# AD9910_Finished_3rd.net
KiCad netlist of a schematic drawn in EAGLE
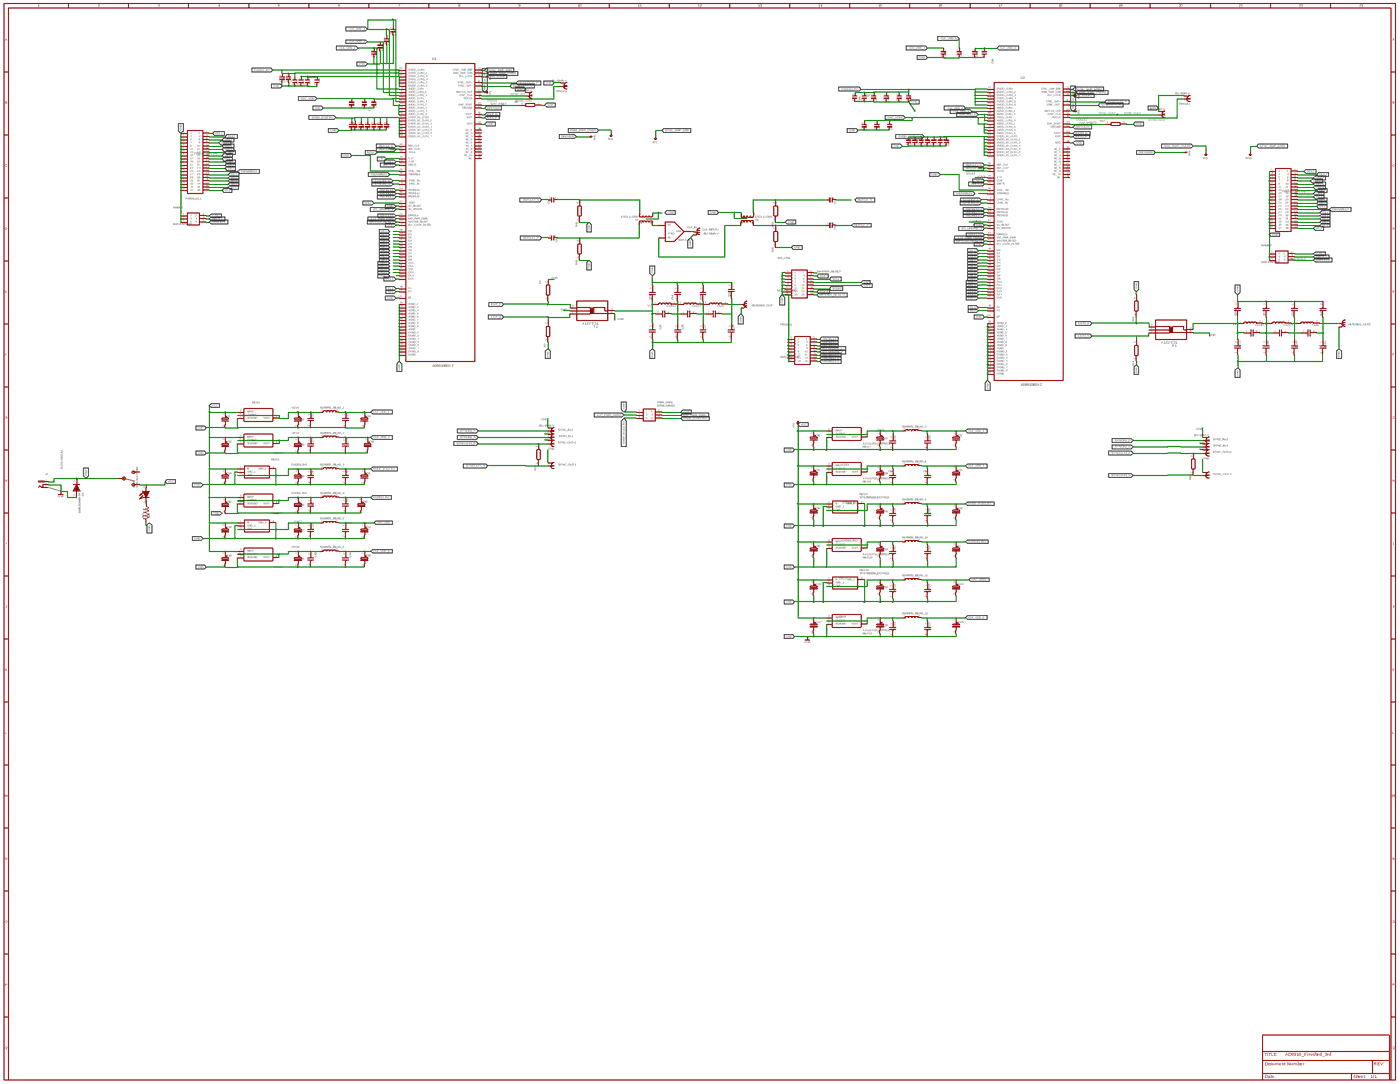
[diagram p0: schematic, sheet 1, overview]
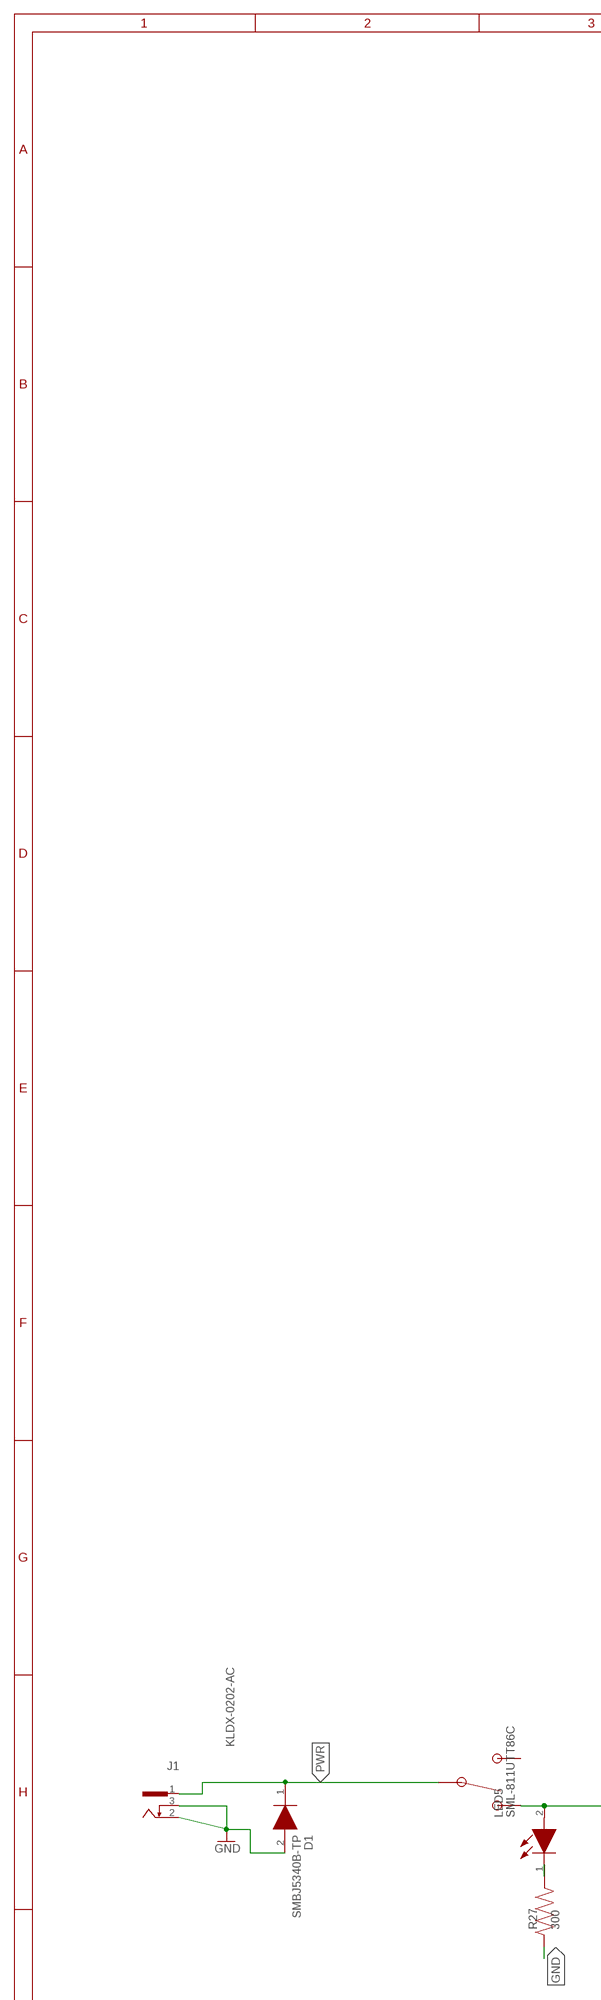
[diagram p1: schematic, sheet 1, part 1 of 7]
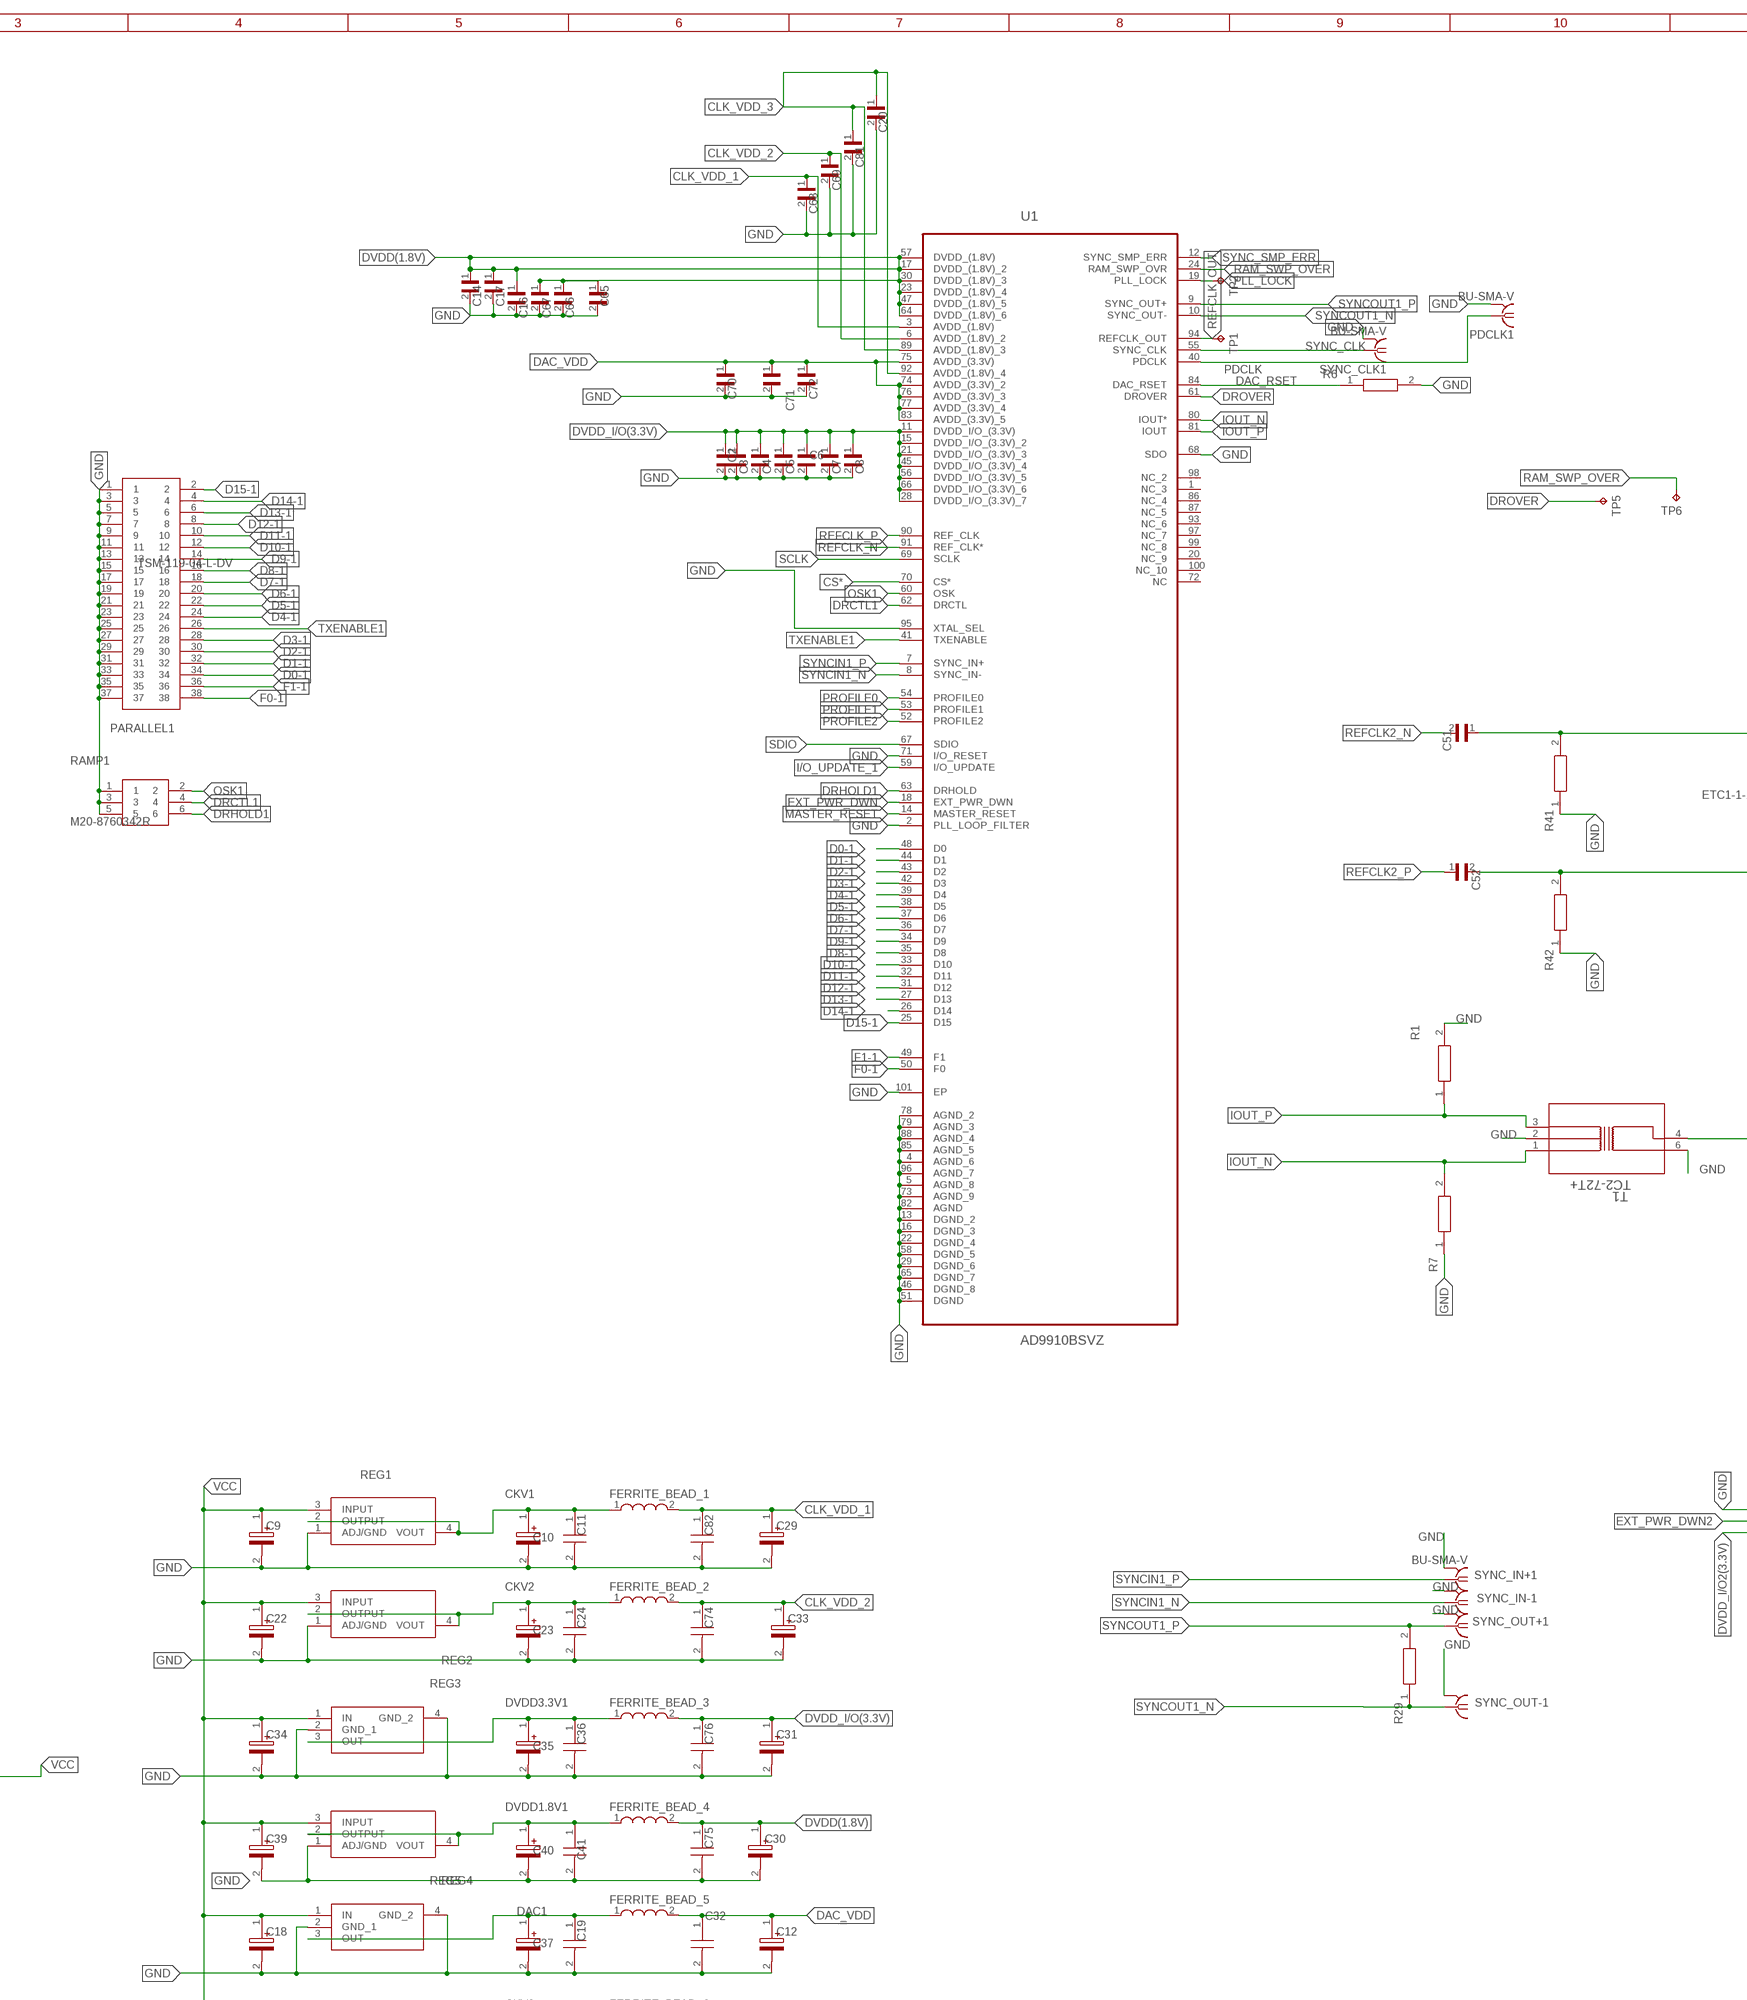
[diagram p2: schematic, sheet 1, part 2 of 7]
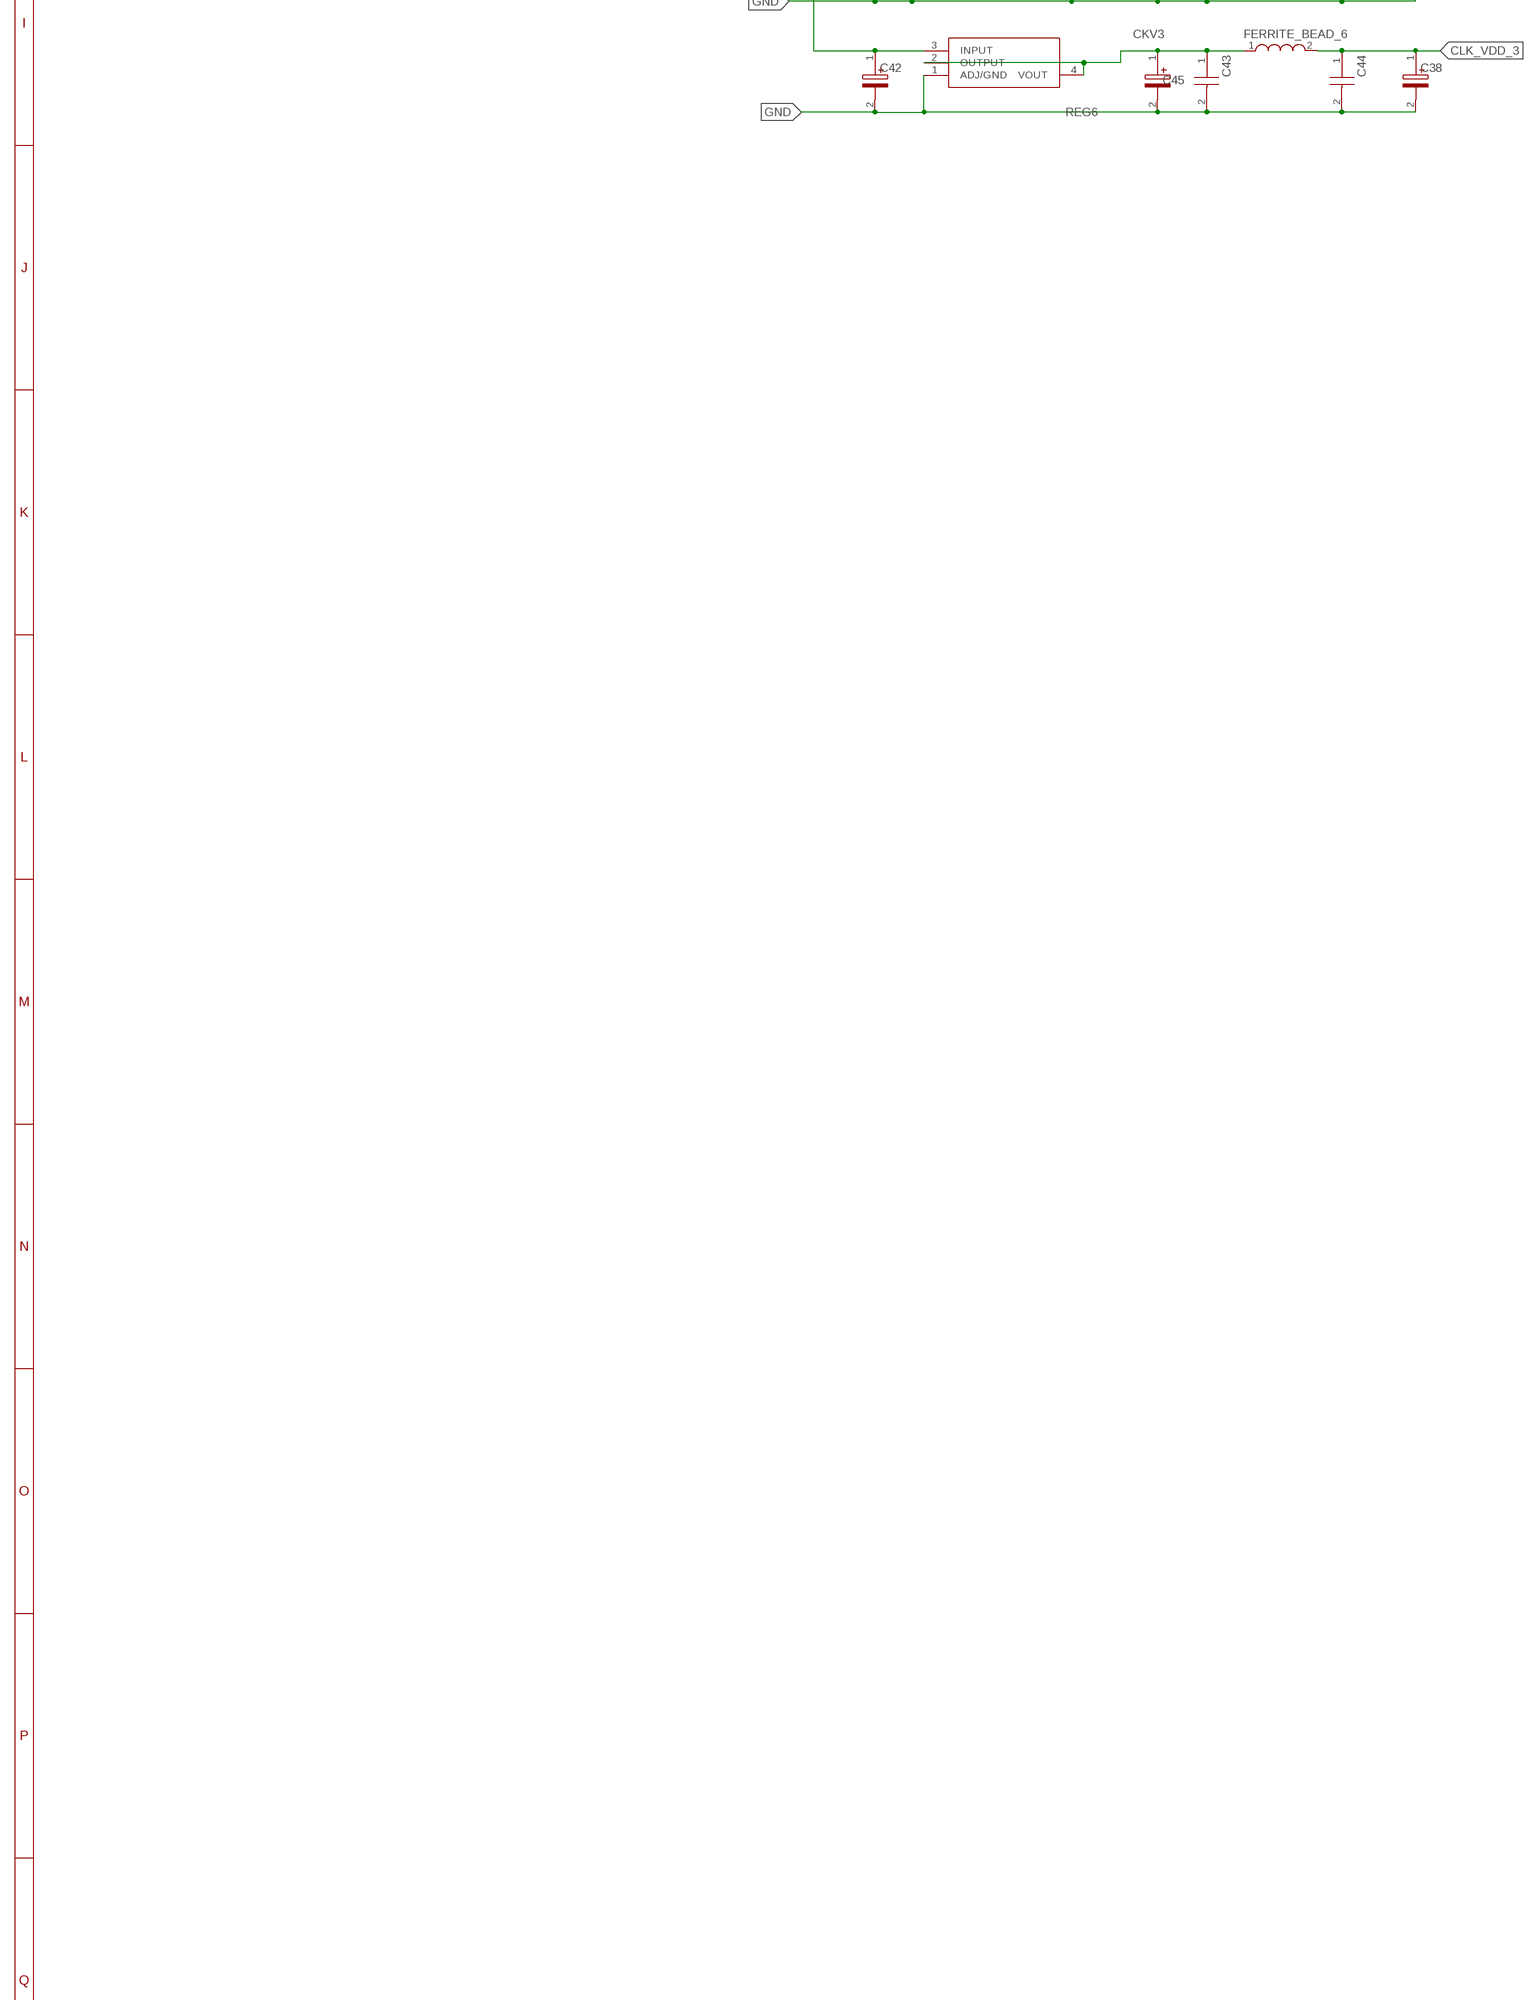
[diagram p3: schematic, sheet 1, part 3 of 7]
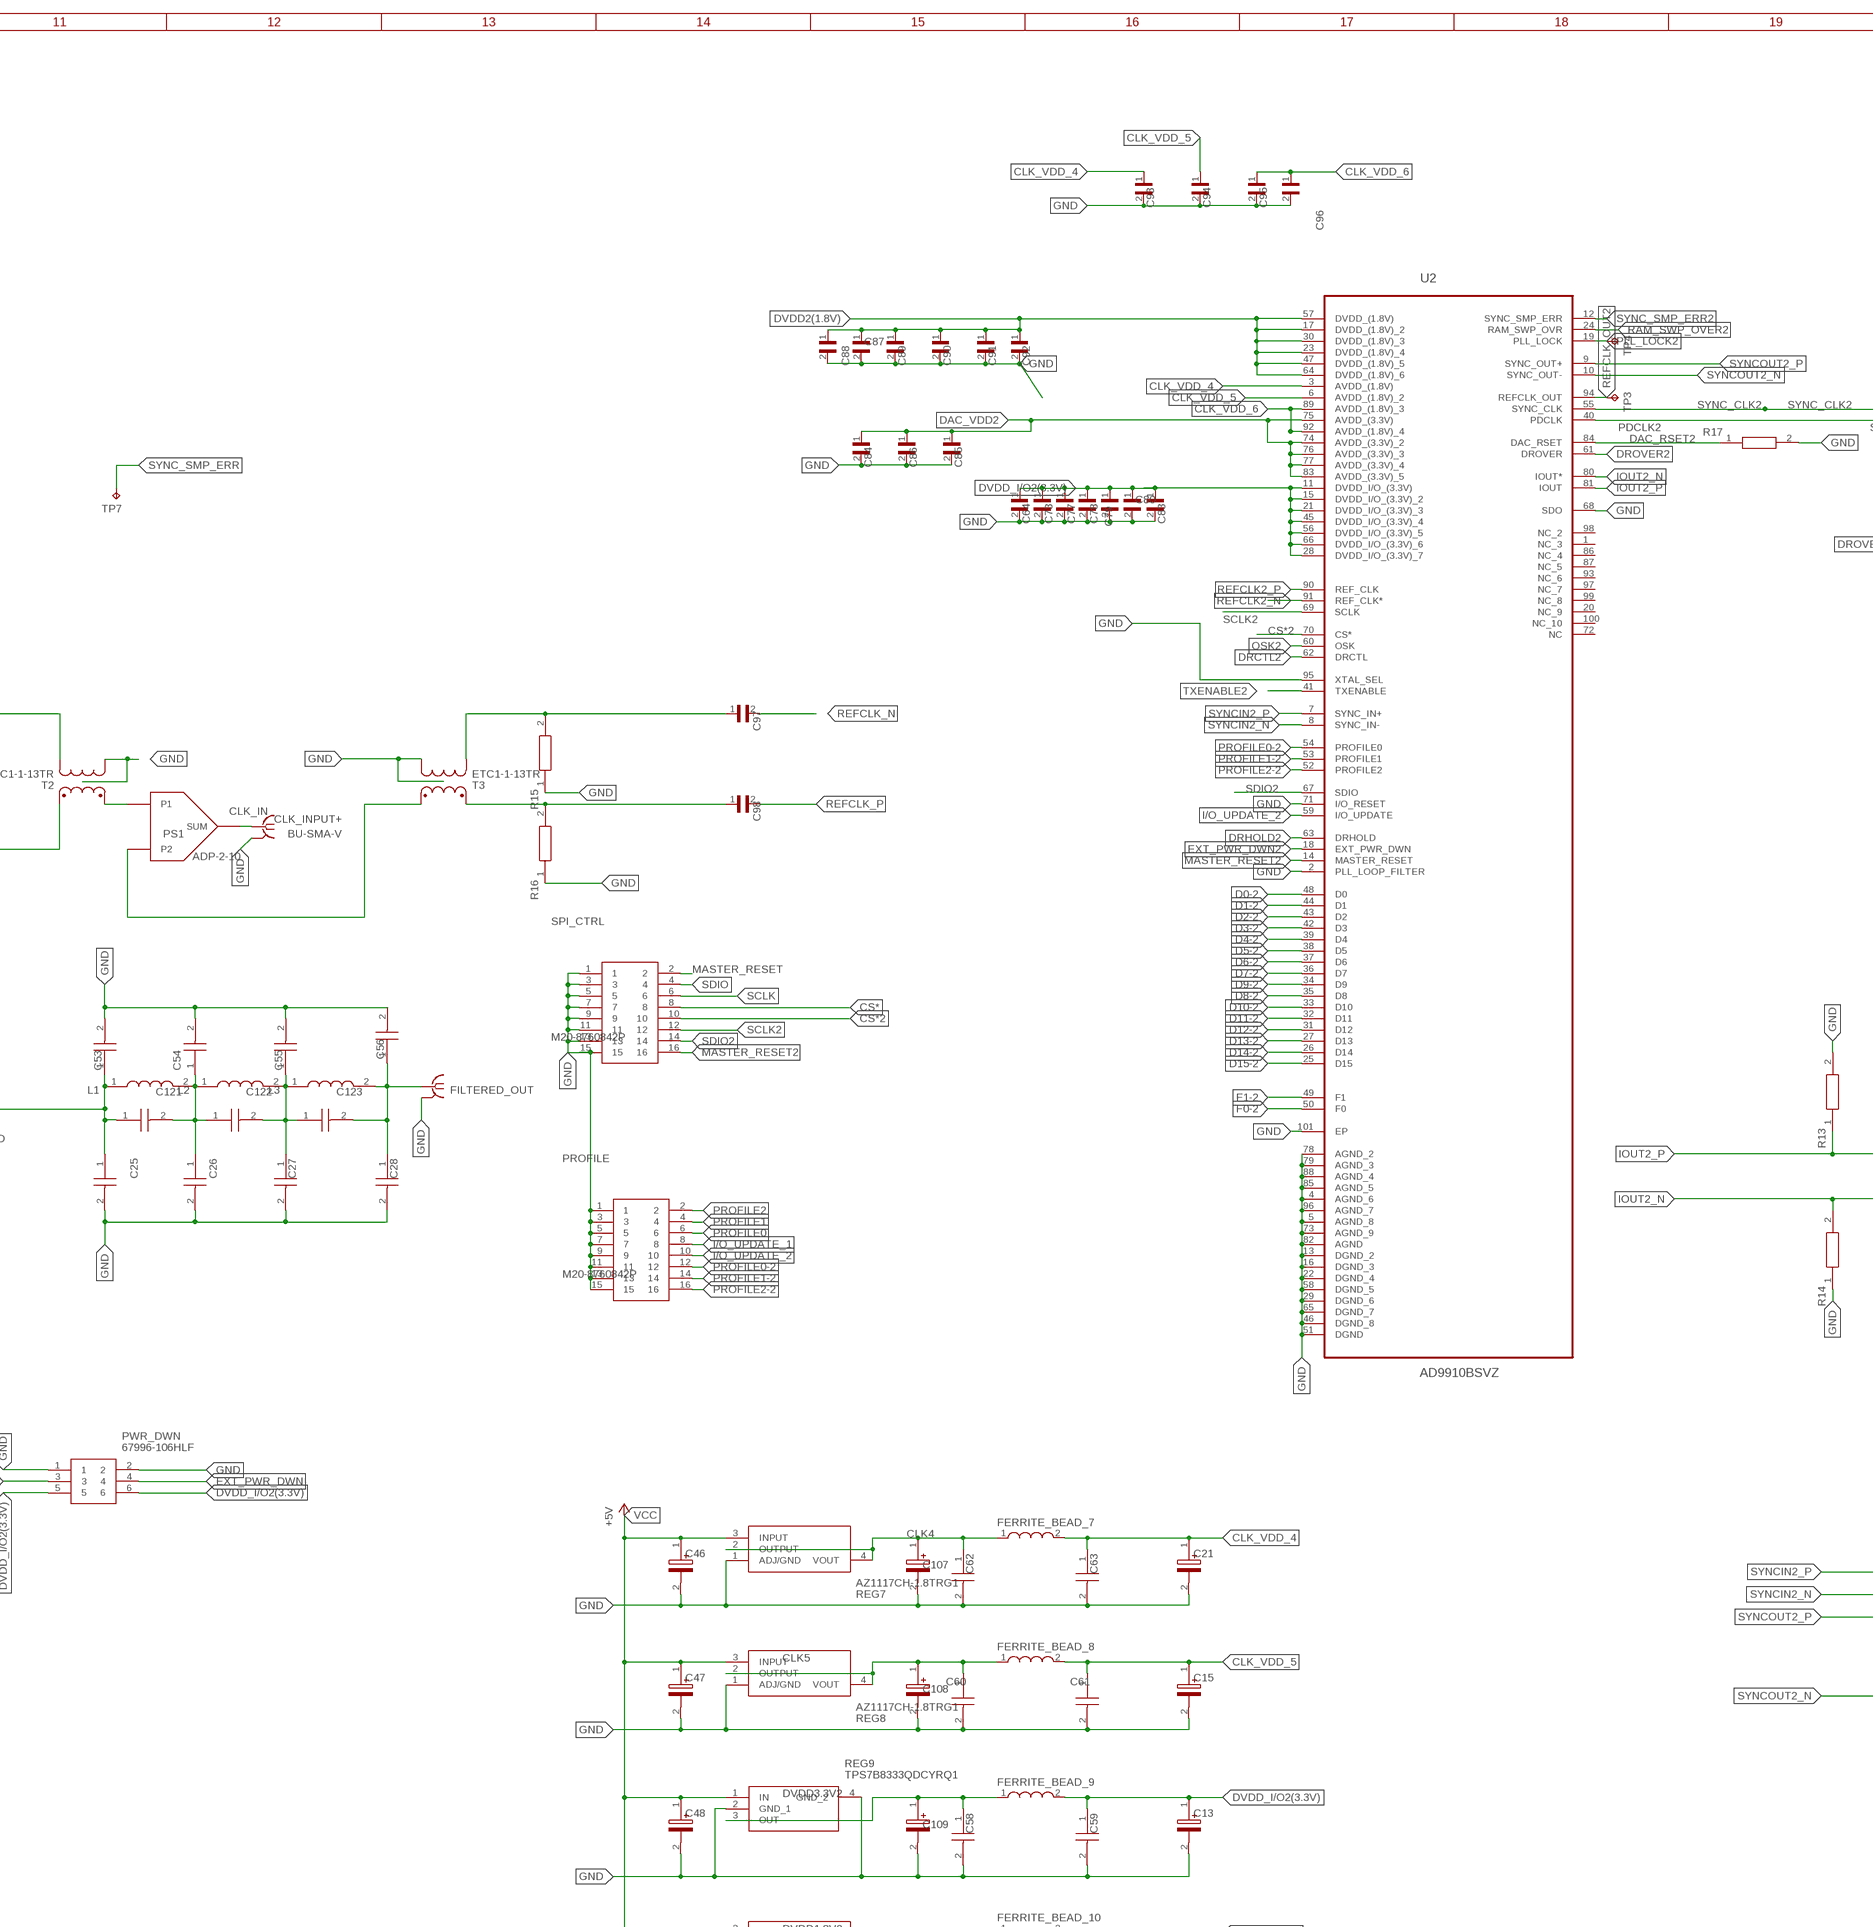
[diagram p4: schematic, sheet 1, part 4 of 7]
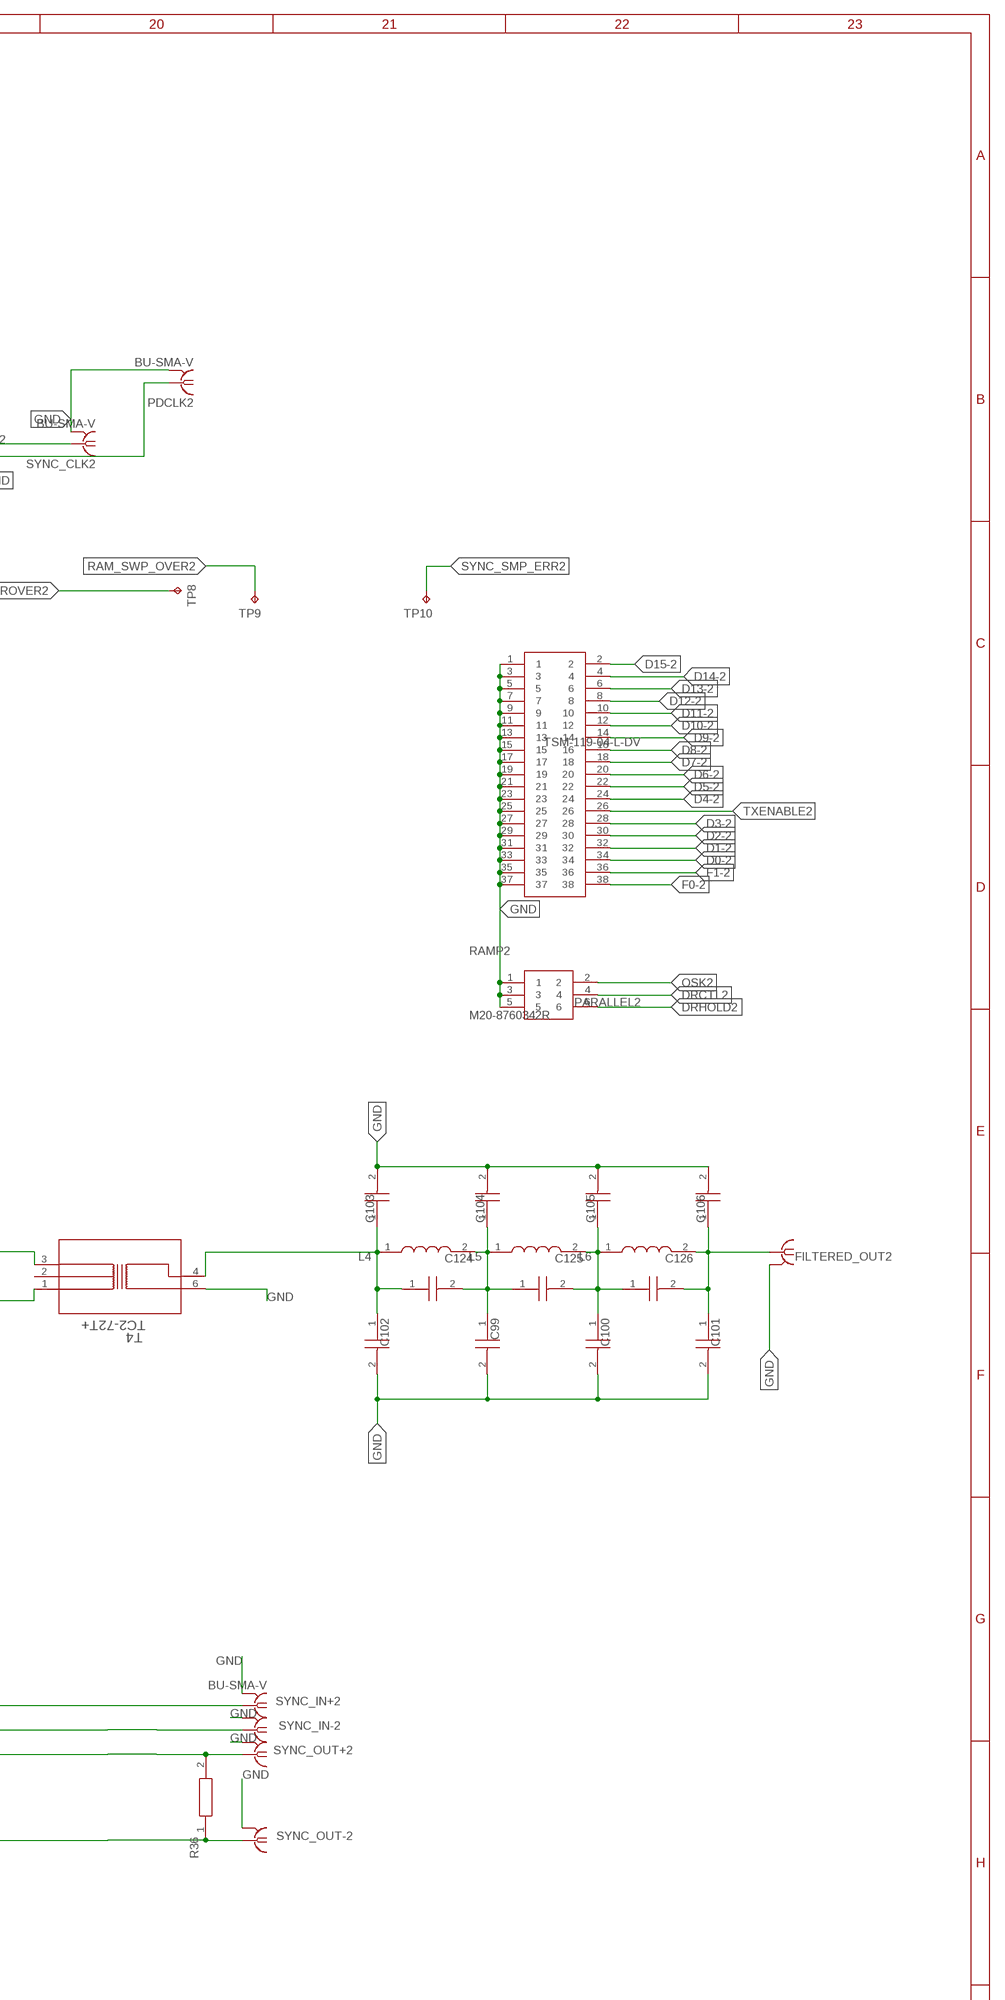
[diagram p5: schematic, sheet 1, part 5 of 7]
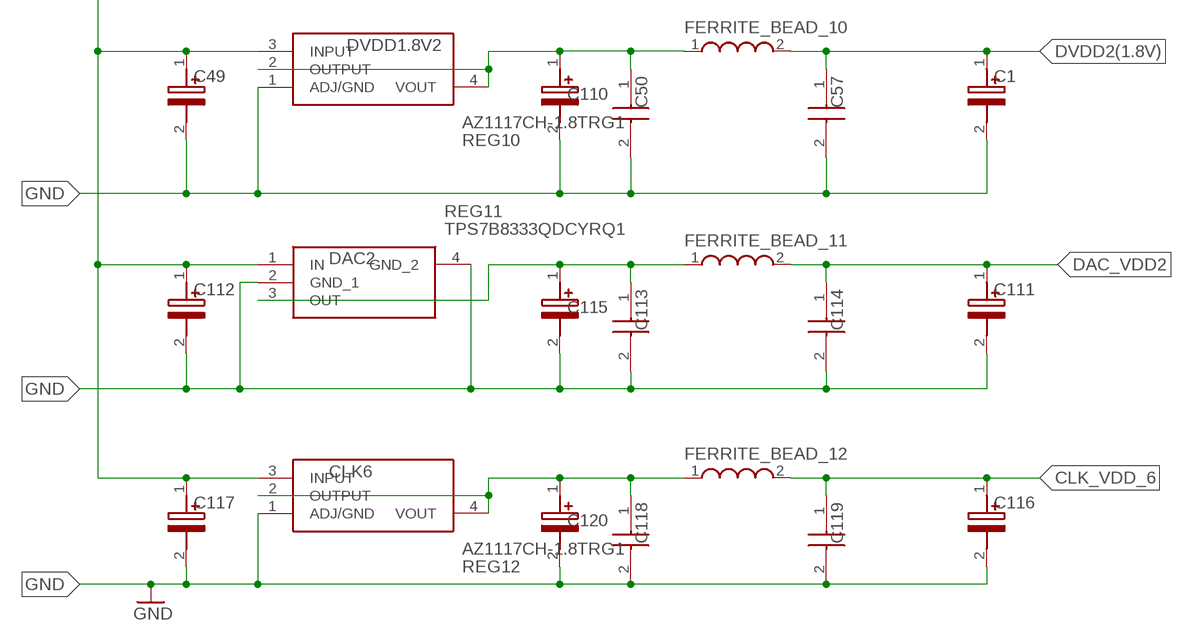
[diagram p6: schematic, sheet 1, part 6 of 7]
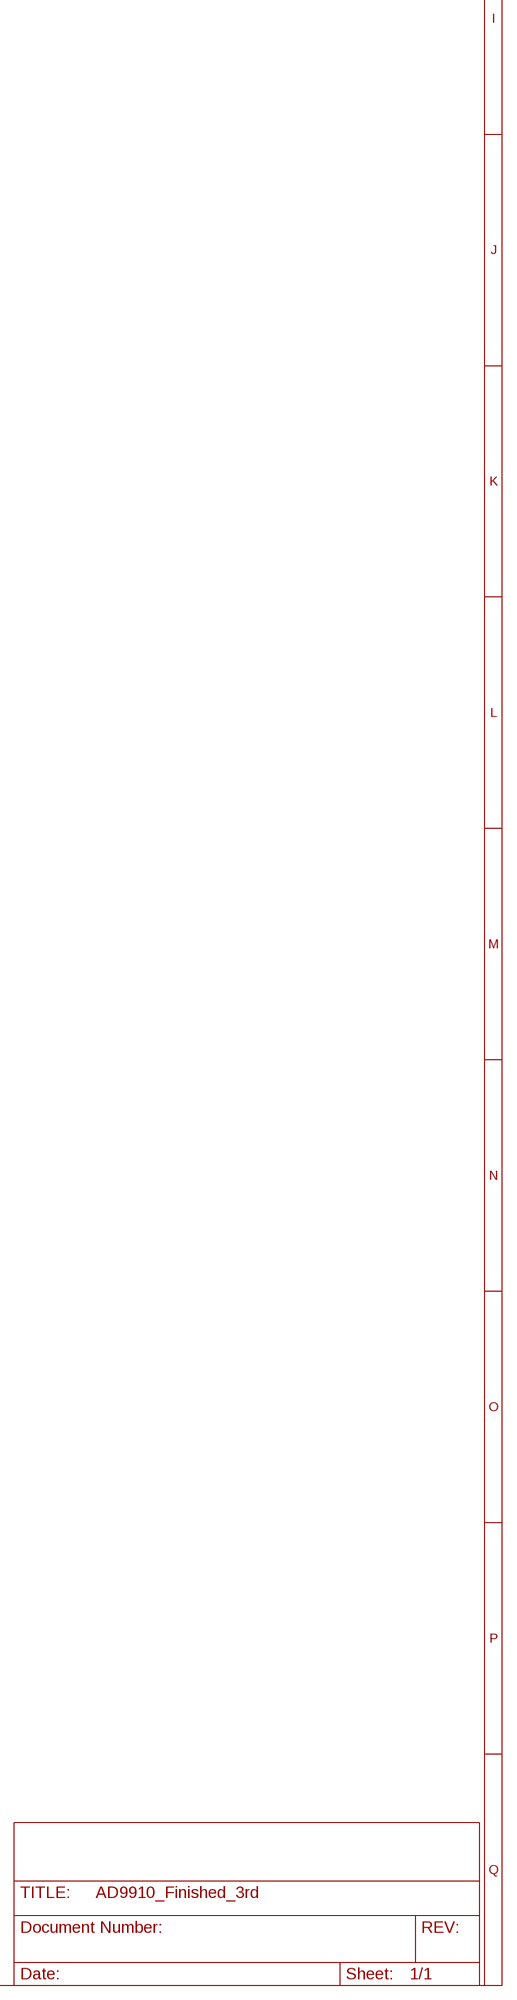
[diagram p7: schematic, sheet 1, part 7 of 7]

(export (version "E")
  (design (tool "Eeschema 10.0.6"))
  (components
    (comp (ref "C1")
      (value "T489A106K010ATA2K2")
      (footprint "eagle-import:CAPPM3216X180N")
      (fields (field (name "MOUSER_PART_NUMBER") "80-T489A106K10ATA2K2"))
      (libsource (lib "eagle-import") (part "T489A106K010ATA2K2"))
    )
    (comp (ref "C2")
      (value "GRM022R60G104ME15L")
      (footprint "eagle-import:CAPC0402X22N")
      (fields (field (name "MF") "Murata"))
      (libsource (lib "eagle-import") (part "GRM022R60G104ME15L"))
    )
    (comp (ref "C3")
      (value "GRM022R60G104ME15L")
      (footprint "eagle-import:CAPC0402X22N")
      (fields (field (name "MF") "Murata"))
      (libsource (lib "eagle-import") (part "GRM022R60G104ME15L"))
    )
    (comp (ref "C4")
      (value "GRM022R60G104ME15L")
      (footprint "eagle-import:CAPC0402X22N")
      (fields (field (name "MF") "Murata"))
      (libsource (lib "eagle-import") (part "GRM022R60G104ME15L"))
    )
    (comp (ref "C5")
      (value "GRM022R60G104ME15L")
      (footprint "eagle-import:CAPC0402X22N")
      (fields (field (name "MF") "Murata"))
      (libsource (lib "eagle-import") (part "GRM022R60G104ME15L"))
    )
    (comp (ref "C6")
      (value "GRM022R60G104ME15L")
      (footprint "eagle-import:CAPC0402X22N")
      (fields (field (name "MF") "Murata"))
      (libsource (lib "eagle-import") (part "GRM022R60G104ME15L"))
    )
    (comp (ref "C7")
      (value "GRM022R60G104ME15L")
      (footprint "eagle-import:CAPC0402X22N")
      (fields (field (name "MF") "Murata"))
      (libsource (lib "eagle-import") (part "GRM022R60G104ME15L"))
    )
    (comp (ref "C8")
      (value "GRM022R60G104ME15L")
      (footprint "eagle-import:CAPC0402X22N")
      (fields (field (name "MF") "Murata"))
      (libsource (lib "eagle-import") (part "GRM022R60G104ME15L"))
    )
    (comp (ref "C9")
      (value "T489A106K010ATA2K2")
      (footprint "eagle-import:CAPPM3216X180N")
      (fields (field (name "MOUSER_PART_NUMBER") "80-T489A106K10ATA2K2"))
      (libsource (lib "eagle-import") (part "T489A106K010ATA2K2"))
    )
    (comp (ref "C10")
      (value "T491A226K010ATAUTO")
      (footprint "eagle-import:CAPPM3216X180N")
      (fields (field (name "MOUSER_PART_NUMBER") "80-T491A226K10ATAUTO"))
      (libsource (lib "eagle-import") (part "T491A226K010ATAUTO"))
    )
    (comp (ref "C11")
      (value "GRM152D80G105ME15D")
      (footprint "eagle-import:CAPC1005X22N")
      (fields (field (name "MOUSER_PART_NUMBER") "81-GRM152D80G105ME5D"))
      (libsource (lib "eagle-import") (part "GRM152D80G105ME15D"))
    )
    (comp (ref "C12")
      (value "T489A106K010ATA2K2")
      (footprint "eagle-import:CAPPM3216X180N")
      (fields (field (name "MOUSER_PART_NUMBER") "80-T489A106K10ATA2K2"))
      (libsource (lib "eagle-import") (part "T489A106K010ATA2K2"))
    )
    (comp (ref "C13")
      (value "T489A106K010ATA2K2")
      (footprint "eagle-import:CAPPM3216X180N")
      (fields (field (name "MOUSER_PART_NUMBER") "80-T489A106K10ATA2K2"))
      (libsource (lib "eagle-import") (part "T489A106K010ATA2K2"))
    )
    (comp (ref "C14")
      (value "GRM022R60G104ME15L")
      (footprint "eagle-import:CAPC0402X22N")
      (fields (field (name "MF") "Murata"))
      (libsource (lib "eagle-import") (part "GRM022R60G104ME15L"))
    )
    (comp (ref "C15")
      (value "T489A106K010ATA2K2")
      (footprint "eagle-import:CAPPM3216X180N")
      (fields (field (name "MOUSER_PART_NUMBER") "80-T489A106K10ATA2K2"))
      (libsource (lib "eagle-import") (part "T489A106K010ATA2K2"))
    )
    (comp (ref "C16")
      (value "GRM022R60G104ME15L")
      (footprint "eagle-import:CAPC0402X22N")
      (fields (field (name "MF") "Murata"))
      (libsource (lib "eagle-import") (part "GRM022R60G104ME15L"))
    )
    (comp (ref "C17")
      (value "GRM022R60G104ME15L")
      (footprint "eagle-import:CAPC0402X22N")
      (fields (field (name "MF") "Murata"))
      (libsource (lib "eagle-import") (part "GRM022R60G104ME15L"))
    )
    (comp (ref "C18")
      (value "T489A106K010ATA2K2")
      (footprint "eagle-import:CAPPM3216X180N")
      (fields (field (name "MOUSER_PART_NUMBER") "80-T489A106K10ATA2K2"))
      (libsource (lib "eagle-import") (part "T489A106K010ATA2K2"))
    )
    (comp (ref "C19")
      (value "GRM152D80G105ME15D")
      (footprint "eagle-import:CAPC1005X22N")
      (fields (field (name "MOUSER_PART_NUMBER") "81-GRM152D80G105ME5D"))
      (libsource (lib "eagle-import") (part "GRM152D80G105ME15D"))
    )
    (comp (ref "C20")
      (value "GRM022R60G104ME15L")
      (footprint "eagle-import:CAPC0402X22N")
      (fields (field (name "MF") "Murata"))
      (libsource (lib "eagle-import") (part "GRM022R60G104ME15L"))
    )
    (comp (ref "C21")
      (value "T489A106K010ATA2K2")
      (footprint "eagle-import:CAPPM3216X180N")
      (fields (field (name "MOUSER_PART_NUMBER") "80-T489A106K10ATA2K2"))
      (libsource (lib "eagle-import") (part "T489A106K010ATA2K2"))
    )
    (comp (ref "C22")
      (value "T489A106K010ATA2K2")
      (footprint "eagle-import:CAPPM3216X180N")
      (fields (field (name "MOUSER_PART_NUMBER") "80-T489A106K10ATA2K2"))
      (libsource (lib "eagle-import") (part "T489A106K010ATA2K2"))
    )
    (comp (ref "C23")
      (value "T491A226K010ATAUTO")
      (footprint "eagle-import:CAPPM3216X180N")
      (fields (field (name "MOUSER_PART_NUMBER") "80-T491A226K10ATAUTO"))
      (libsource (lib "eagle-import") (part "T491A226K010ATAUTO"))
    )
    (comp (ref "C24")
      (value "GRM152D80G105ME15D")
      (footprint "eagle-import:CAPC1005X22N")
      (fields (field (name "MOUSER_PART_NUMBER") "81-GRM152D80G105ME5D"))
      (libsource (lib "eagle-import") (part "GRM152D80G105ME15D"))
    )
    (comp (ref "C25")
      (value "GQM2195C2E2R7CB12D")
      (footprint "eagle-import:CAPC2012X100N")
      (fields (field (name "MOUSER_PART_NUMBER") "81-GQM2195C2E2R7CB2D"))
      (libsource (lib "eagle-import") (part "GQM2195C2E2R7CB12D"))
    )
    (comp (ref "C26")
      (value "GQM2195C2E5R6CB12D")
      (footprint "eagle-import:CAPC2012X100N")
      (fields (field (name "MOUSER_PART_NUMBER") "81-GQM2195C2E5R6CB2D"))
      (libsource (lib "eagle-import") (part "GQM2195C2E5R6CB12D"))
    )
    (comp (ref "C27")
      (value "GQM2195C2E6R8CB12D")
      (footprint "eagle-import:CAPC2012X100N")
      (fields (field (name "MOUSER_PART_NUMBER") "81-GQM2195C2E6R8CB2D"))
      (libsource (lib "eagle-import") (part "GQM2195C2E6R8CB12D"))
    )
    (comp (ref "C28")
      (value "GQM2195C2E3R9BB12D")
      (footprint "eagle-import:CAPC2012X100N")
      (libsource (lib "eagle-import") (part "GQM2195C2E3R9BB12D"))
    )
    (comp (ref "C29")
      (value "T489A106K010ATA2K2")
      (footprint "eagle-import:CAPPM3216X180N")
      (fields (field (name "MOUSER_PART_NUMBER") "80-T489A106K10ATA2K2"))
      (libsource (lib "eagle-import") (part "T489A106K010ATA2K2"))
    )
    (comp (ref "C30")
      (value "T489A106K010ATA2K2")
      (footprint "eagle-import:CAPPM3216X180N")
      (fields (field (name "MOUSER_PART_NUMBER") "80-T489A106K10ATA2K2"))
      (libsource (lib "eagle-import") (part "T489A106K010ATA2K2"))
    )
    (comp (ref "C31")
      (value "T489A106K010ATA2K2")
      (footprint "eagle-import:CAPPM3216X180N")
      (fields (field (name "MOUSER_PART_NUMBER") "80-T489A106K10ATA2K2"))
      (libsource (lib "eagle-import") (part "T489A106K010ATA2K2"))
    )
    (comp (ref "C32")
      (value "GRM152D80G105ME15D")
      (footprint "eagle-import:CAPC1005X22N")
      (fields (field (name "MOUSER_PART_NUMBER") "81-GRM152D80G105ME5D"))
      (libsource (lib "eagle-import") (part "GRM152D80G105ME15D"))
    )
    (comp (ref "C33")
      (value "T489A106K010ATA2K2")
      (footprint "eagle-import:CAPPM3216X180N")
      (fields (field (name "MOUSER_PART_NUMBER") "80-T489A106K10ATA2K2"))
      (libsource (lib "eagle-import") (part "T489A106K010ATA2K2"))
    )
    (comp (ref "C34")
      (value "T489A106K010ATA2K2")
      (footprint "eagle-import:CAPPM3216X180N")
      (fields (field (name "MOUSER_PART_NUMBER") "80-T489A106K10ATA2K2"))
      (libsource (lib "eagle-import") (part "T489A106K010ATA2K2"))
    )
    (comp (ref "C35")
      (value "T491A226K010ATAUTO")
      (footprint "eagle-import:CAPPM3216X180N")
      (fields (field (name "MOUSER_PART_NUMBER") "80-T491A226K10ATAUTO"))
      (libsource (lib "eagle-import") (part "T491A226K010ATAUTO"))
    )
    (comp (ref "C36")
      (value "GRM152D80G105ME15D")
      (footprint "eagle-import:CAPC1005X22N")
      (fields (field (name "MOUSER_PART_NUMBER") "81-GRM152D80G105ME5D"))
      (libsource (lib "eagle-import") (part "GRM152D80G105ME15D"))
    )
    (comp (ref "C37")
      (value "T491A226K010ATAUTO")
      (footprint "eagle-import:CAPPM3216X180N")
      (fields (field (name "MOUSER_PART_NUMBER") "80-T491A226K10ATAUTO"))
      (libsource (lib "eagle-import") (part "T491A226K010ATAUTO"))
    )
    (comp (ref "C38")
      (value "T489A106K010ATA2K2")
      (footprint "eagle-import:CAPPM3216X180N")
      (fields (field (name "MOUSER_PART_NUMBER") "80-T489A106K10ATA2K2"))
      (libsource (lib "eagle-import") (part "T489A106K010ATA2K2"))
    )
    (comp (ref "C39")
      (value "T489A106K010ATA2K2")
      (footprint "eagle-import:CAPPM3216X180N")
      (fields (field (name "MOUSER_PART_NUMBER") "80-T489A106K10ATA2K2"))
      (libsource (lib "eagle-import") (part "T489A106K010ATA2K2"))
    )
    (comp (ref "C40")
      (value "T491A226K010ATAUTO")
      (footprint "eagle-import:CAPPM3216X180N")
      (fields (field (name "MOUSER_PART_NUMBER") "80-T491A226K10ATAUTO"))
      (libsource (lib "eagle-import") (part "T491A226K010ATAUTO"))
    )
    (comp (ref "C41")
      (value "GRM152D80G105ME15D")
      (footprint "eagle-import:CAPC1005X22N")
      (fields (field (name "MOUSER_PART_NUMBER") "81-GRM152D80G105ME5D"))
      (libsource (lib "eagle-import") (part "GRM152D80G105ME15D"))
    )
    (comp (ref "C42")
      (value "T489A106K010ATA2K2")
      (footprint "eagle-import:CAPPM3216X180N")
      (fields (field (name "MOUSER_PART_NUMBER") "80-T489A106K10ATA2K2"))
      (libsource (lib "eagle-import") (part "T489A106K010ATA2K2"))
    )
    (comp (ref "C43")
      (value "GRM152D80G105ME15D")
      (footprint "eagle-import:CAPC1005X22N")
      (fields (field (name "MOUSER_PART_NUMBER") "81-GRM152D80G105ME5D"))
      (libsource (lib "eagle-import") (part "GRM152D80G105ME15D"))
    )
    (comp (ref "C44")
      (value "GRM152D80G105ME15D")
      (footprint "eagle-import:CAPC1005X22N")
      (fields (field (name "MOUSER_PART_NUMBER") "81-GRM152D80G105ME5D"))
      (libsource (lib "eagle-import") (part "GRM152D80G105ME15D"))
    )
    (comp (ref "C45")
      (value "T491A226K010ATAUTO")
      (footprint "eagle-import:CAPPM3216X180N")
      (fields (field (name "MOUSER_PART_NUMBER") "80-T491A226K10ATAUTO"))
      (libsource (lib "eagle-import") (part "T491A226K010ATAUTO"))
    )
    (comp (ref "C46")
      (value "T489A106K010ATA2K2")
      (footprint "eagle-import:CAPPM3216X180N")
      (fields (field (name "MOUSER_PART_NUMBER") "80-T489A106K10ATA2K2"))
      (libsource (lib "eagle-import") (part "T489A106K010ATA2K2"))
    )
    (comp (ref "C47")
      (value "T489A106K010ATA2K2")
      (footprint "eagle-import:CAPPM3216X180N")
      (fields (field (name "MOUSER_PART_NUMBER") "80-T489A106K10ATA2K2"))
      (libsource (lib "eagle-import") (part "T489A106K010ATA2K2"))
    )
    (comp (ref "C48")
      (value "T489A106K010ATA2K2")
      (footprint "eagle-import:CAPPM3216X180N")
      (fields (field (name "MOUSER_PART_NUMBER") "80-T489A106K10ATA2K2"))
      (libsource (lib "eagle-import") (part "T489A106K010ATA2K2"))
    )
    (comp (ref "C49")
      (value "T489A106K010ATA2K2")
      (footprint "eagle-import:CAPPM3216X180N")
      (fields (field (name "MOUSER_PART_NUMBER") "80-T489A106K10ATA2K2"))
      (libsource (lib "eagle-import") (part "T489A106K010ATA2K2"))
    )
    (comp (ref "C50")
      (value "GRMMDXR60J105ME05D")
      (footprint "eagle-import:CAPC0502X28N")
      (fields (field (name "MOUSER_PART_NUMBER") "81-GRMMDXR60J105ME5D"))
      (libsource (lib "eagle-import") (part "GRMMDXR60J105ME05D"))
    )
    (comp (ref "C51")
      (value "GRM022R60G104ME15L")
      (footprint "eagle-import:CAPC0402X22N")
      (fields (field (name "MF") "Murata"))
      (libsource (lib "eagle-import") (part "GRM022R60G104ME15L"))
    )
    (comp (ref "C52")
      (value "GRM022R60G104ME15L")
      (footprint "eagle-import:CAPC0402X22N")
      (fields (field (name "MF") "Murata"))
      (libsource (lib "eagle-import") (part "GRM022R60G104ME15L"))
    )
    (comp (ref "C53")
      (value "GQM2195C2E2R7CB12D")
      (footprint "eagle-import:CAPC2012X100N")
      (fields (field (name "MOUSER_PART_NUMBER") "81-GQM2195C2E2R7CB2D"))
      (libsource (lib "eagle-import") (part "GQM2195C2E2R7CB12D"))
    )
    (comp (ref "C54")
      (value "GQM2195C2E5R6CB12D")
      (footprint "eagle-import:CAPC2012X100N")
      (fields (field (name "MOUSER_PART_NUMBER") "81-GQM2195C2E5R6CB2D"))
      (libsource (lib "eagle-import") (part "GQM2195C2E5R6CB12D"))
    )
    (comp (ref "C55")
      (value "GQM2195C2E6R8CB12D")
      (footprint "eagle-import:CAPC2012X100N")
      (fields (field (name "MOUSER_PART_NUMBER") "81-GQM2195C2E6R8CB2D"))
      (libsource (lib "eagle-import") (part "GQM2195C2E6R8CB12D"))
    )
    (comp (ref "C56")
      (value "GQM2195C2E3R9BB12D")
      (footprint "eagle-import:CAPC2012X100N")
      (libsource (lib "eagle-import") (part "GQM2195C2E3R9BB12D"))
    )
    (comp (ref "C57")
      (value "GRMMDXR60J105ME05D")
      (footprint "eagle-import:CAPC0502X28N")
      (fields (field (name "MOUSER_PART_NUMBER") "81-GRMMDXR60J105ME5D"))
      (libsource (lib "eagle-import") (part "GRMMDXR60J105ME05D"))
    )
    (comp (ref "C58")
      (value "GRMMDXR60J105ME05D")
      (footprint "eagle-import:CAPC0502X28N")
      (fields (field (name "MOUSER_PART_NUMBER") "81-GRMMDXR60J105ME5D"))
      (libsource (lib "eagle-import") (part "GRMMDXR60J105ME05D"))
    )
    (comp (ref "C59")
      (value "GRMMDXR60J105ME05D")
      (footprint "eagle-import:CAPC0502X28N")
      (fields (field (name "MOUSER_PART_NUMBER") "81-GRMMDXR60J105ME5D"))
      (libsource (lib "eagle-import") (part "GRMMDXR60J105ME05D"))
    )
    (comp (ref "C60")
      (value "GRMMDXR60J105ME05D")
      (footprint "eagle-import:CAPC0502X28N")
      (fields (field (name "MOUSER_PART_NUMBER") "81-GRMMDXR60J105ME5D"))
      (libsource (lib "eagle-import") (part "GRMMDXR60J105ME05D"))
    )
    (comp (ref "C61")
      (value "GRMMDXR60J105ME05D")
      (footprint "eagle-import:CAPC0502X28N")
      (fields (field (name "MOUSER_PART_NUMBER") "81-GRMMDXR60J105ME5D"))
      (libsource (lib "eagle-import") (part "GRMMDXR60J105ME05D"))
    )
    (comp (ref "C62")
      (value "GRMMDXR60J105ME05D")
      (footprint "eagle-import:CAPC0502X28N")
      (fields (field (name "MOUSER_PART_NUMBER") "81-GRMMDXR60J105ME5D"))
      (libsource (lib "eagle-import") (part "GRMMDXR60J105ME05D"))
    )
    (comp (ref "C63")
      (value "GRMMDXR60J105ME05D")
      (footprint "eagle-import:CAPC0502X28N")
      (fields (field (name "MOUSER_PART_NUMBER") "81-GRMMDXR60J105ME5D"))
      (libsource (lib "eagle-import") (part "GRMMDXR60J105ME05D"))
    )
    (comp (ref "C64")
      (value "GRM022R60G104ME15L")
      (footprint "eagle-import:CAPC0402X22N")
      (fields (field (name "MF") "Murata"))
      (libsource (lib "eagle-import") (part "GRM022R60G104ME15L"))
    )
    (comp (ref "C65")
      (value "GRM022R60G104ME15L")
      (footprint "eagle-import:CAPC0402X22N")
      (fields (field (name "MF") "Murata"))
      (libsource (lib "eagle-import") (part "GRM022R60G104ME15L"))
    )
    (comp (ref "C66")
      (value "GRM022R60G104ME15L")
      (footprint "eagle-import:CAPC0402X22N")
      (fields (field (name "MF") "Murata"))
      (libsource (lib "eagle-import") (part "GRM022R60G104ME15L"))
    )
    (comp (ref "C67")
      (value "GRM022R60G104ME15L")
      (footprint "eagle-import:CAPC0402X22N")
      (fields (field (name "MF") "Murata"))
      (libsource (lib "eagle-import") (part "GRM022R60G104ME15L"))
    )
    (comp (ref "C68")
      (value "GRM022R60G104ME15L")
      (footprint "eagle-import:CAPC0402X22N")
      (fields (field (name "MF") "Murata"))
      (libsource (lib "eagle-import") (part "GRM022R60G104ME15L"))
    )
    (comp (ref "C69")
      (value "GRM022R60G104ME15L")
      (footprint "eagle-import:CAPC0402X22N")
      (fields (field (name "MF") "Murata"))
      (libsource (lib "eagle-import") (part "GRM022R60G104ME15L"))
    )
    (comp (ref "C70")
      (value "GRM022R60G104ME15L")
      (footprint "eagle-import:CAPC0402X22N")
      (fields (field (name "MF") "Murata"))
      (libsource (lib "eagle-import") (part "GRM022R60G104ME15L"))
    )
    (comp (ref "C71")
      (value "GRM022R60G104ME15L")
      (footprint "eagle-import:CAPC0402X22N")
      (fields (field (name "MF") "Murata"))
      (libsource (lib "eagle-import") (part "GRM022R60G104ME15L"))
    )
    (comp (ref "C72")
      (value "GRM022R60G104ME15L")
      (footprint "eagle-import:CAPC0402X22N")
      (fields (field (name "MF") "Murata"))
      (libsource (lib "eagle-import") (part "GRM022R60G104ME15L"))
    )
    (comp (ref "C73")
      (value "GRM022R60G104ME15L")
      (footprint "eagle-import:CAPC0402X22N")
      (fields (field (name "MF") "Murata"))
      (libsource (lib "eagle-import") (part "GRM022R60G104ME15L"))
    )
    (comp (ref "C74")
      (value "GRM152D80G105ME15D")
      (footprint "eagle-import:CAPC1005X22N")
      (fields (field (name "MOUSER_PART_NUMBER") "81-GRM152D80G105ME5D"))
      (libsource (lib "eagle-import") (part "GRM152D80G105ME15D"))
    )
    (comp (ref "C75")
      (value "GRM152D80G105ME15D")
      (footprint "eagle-import:CAPC1005X22N")
      (fields (field (name "MOUSER_PART_NUMBER") "81-GRM152D80G105ME5D"))
      (libsource (lib "eagle-import") (part "GRM152D80G105ME15D"))
    )
    (comp (ref "C76")
      (value "GRM152D80G105ME15D")
      (footprint "eagle-import:CAPC1005X22N")
      (fields (field (name "MOUSER_PART_NUMBER") "81-GRM152D80G105ME5D"))
      (libsource (lib "eagle-import") (part "GRM152D80G105ME15D"))
    )
    (comp (ref "C77")
      (value "GRM022R60G104ME15L")
      (footprint "eagle-import:CAPC0402X22N")
      (fields (field (name "MF") "Murata"))
      (libsource (lib "eagle-import") (part "GRM022R60G104ME15L"))
    )
    (comp (ref "C78")
      (value "GRM022R60G104ME15L")
      (footprint "eagle-import:CAPC0402X22N")
      (fields (field (name "MF") "Murata"))
      (libsource (lib "eagle-import") (part "GRM022R60G104ME15L"))
    )
    (comp (ref "C79")
      (value "GRM022R60G104ME15L")
      (footprint "eagle-import:CAPC0402X22N")
      (fields (field (name "MF") "Murata"))
      (libsource (lib "eagle-import") (part "GRM022R60G104ME15L"))
    )
    (comp (ref "C80")
      (value "GRM022R60G104ME15L")
      (footprint "eagle-import:CAPC0402X22N")
      (fields (field (name "MF") "Murata"))
      (libsource (lib "eagle-import") (part "GRM022R60G104ME15L"))
    )
    (comp (ref "C81")
      (value "GRM022R60G104ME15L")
      (footprint "eagle-import:CAPC0402X22N")
      (fields (field (name "MF") "Murata"))
      (libsource (lib "eagle-import") (part "GRM022R60G104ME15L"))
    )
    (comp (ref "C82")
      (value "GRM152D80G105ME15D")
      (footprint "eagle-import:CAPC1005X22N")
      (fields (field (name "MOUSER_PART_NUMBER") "81-GRM152D80G105ME5D"))
      (libsource (lib "eagle-import") (part "GRM152D80G105ME15D"))
    )
    (comp (ref "C83")
      (value "GRM022R60G104ME15L")
      (footprint "eagle-import:CAPC0402X22N")
      (fields (field (name "MF") "Murata"))
      (libsource (lib "eagle-import") (part "GRM022R60G104ME15L"))
    )
    (comp (ref "C84")
      (value "GRM022R60G104ME15L")
      (footprint "eagle-import:CAPC0402X22N")
      (fields (field (name "MF") "Murata"))
      (libsource (lib "eagle-import") (part "GRM022R60G104ME15L"))
    )
    (comp (ref "C85")
      (value "GRM022R60G104ME15L")
      (footprint "eagle-import:CAPC0402X22N")
      (fields (field (name "MF") "Murata"))
      (libsource (lib "eagle-import") (part "GRM022R60G104ME15L"))
    )
    (comp (ref "C86")
      (value "GRM022R60G104ME15L")
      (footprint "eagle-import:CAPC0402X22N")
      (fields (field (name "MF") "Murata"))
      (libsource (lib "eagle-import") (part "GRM022R60G104ME15L"))
    )
    (comp (ref "C87")
      (value "GRM022R60G104ME15L")
      (footprint "eagle-import:CAPC0402X22N")
      (fields (field (name "MF") "Murata"))
      (libsource (lib "eagle-import") (part "GRM022R60G104ME15L"))
    )
    (comp (ref "C88")
      (value "GRM022R60G104ME15L")
      (footprint "eagle-import:CAPC0402X22N")
      (fields (field (name "MF") "Murata"))
      (libsource (lib "eagle-import") (part "GRM022R60G104ME15L"))
    )
    (comp (ref "C89")
      (value "GRM022R60G104ME15L")
      (footprint "eagle-import:CAPC0402X22N")
      (fields (field (name "MF") "Murata"))
      (libsource (lib "eagle-import") (part "GRM022R60G104ME15L"))
    )
    (comp (ref "C90")
      (value "GRM022R60G104ME15L")
      (footprint "eagle-import:CAPC0402X22N")
      (fields (field (name "MF") "Murata"))
      (libsource (lib "eagle-import") (part "GRM022R60G104ME15L"))
    )
    (comp (ref "C91")
      (value "GRM022R60G104ME15L")
      (footprint "eagle-import:CAPC0402X22N")
      (fields (field (name "MF") "Murata"))
      (libsource (lib "eagle-import") (part "GRM022R60G104ME15L"))
    )
    (comp (ref "C92")
      (value "GRM022R60G104ME15L")
      (footprint "eagle-import:CAPC0402X22N")
      (fields (field (name "MF") "Murata"))
      (libsource (lib "eagle-import") (part "GRM022R60G104ME15L"))
    )
    (comp (ref "C93")
      (value "GRM022R60G104ME15L")
      (footprint "eagle-import:CAPC0402X22N")
      (fields (field (name "MF") "Murata"))
      (libsource (lib "eagle-import") (part "GRM022R60G104ME15L"))
    )
    (comp (ref "C94")
      (value "GRM022R60G104ME15L")
      (footprint "eagle-import:CAPC0402X22N")
      (fields (field (name "MF") "Murata"))
      (libsource (lib "eagle-import") (part "GRM022R60G104ME15L"))
    )
    (comp (ref "C95")
      (value "GRM022R60G104ME15L")
      (footprint "eagle-import:CAPC0402X22N")
      (fields (field (name "MF") "Murata"))
      (libsource (lib "eagle-import") (part "GRM022R60G104ME15L"))
    )
    (comp (ref "C96")
      (value "GRM022R60G104ME15L")
      (footprint "eagle-import:CAPC0402X22N")
      (fields (field (name "MF") "Murata"))
      (libsource (lib "eagle-import") (part "GRM022R60G104ME15L"))
    )
    (comp (ref "C97")
      (value "GRM022R60G104ME15L")
      (footprint "eagle-import:CAPC0402X22N")
      (fields (field (name "MF") "Murata"))
      (libsource (lib "eagle-import") (part "GRM022R60G104ME15L"))
    )
    (comp (ref "C98")
      (value "GRM022R60G104ME15L")
      (footprint "eagle-import:CAPC0402X22N")
      (fields (field (name "MF") "Murata"))
      (libsource (lib "eagle-import") (part "GRM022R60G104ME15L"))
    )
    (comp (ref "C99")
      (value "GQM2195C2E5R6CB12D")
      (footprint "eagle-import:CAPC2012X100N")
      (fields (field (name "MOUSER_PART_NUMBER") "81-GQM2195C2E5R6CB2D"))
      (libsource (lib "eagle-import") (part "GQM2195C2E5R6CB12D"))
    )
    (comp (ref "C100")
      (value "GQM2195C2E6R8CB12D")
      (footprint "eagle-import:CAPC2012X100N")
      (fields (field (name "MOUSER_PART_NUMBER") "81-GQM2195C2E6R8CB2D"))
      (libsource (lib "eagle-import") (part "GQM2195C2E6R8CB12D"))
    )
    (comp (ref "C101")
      (value "GQM2195C2E3R9BB12D")
      (footprint "eagle-import:CAPC2012X100N")
      (libsource (lib "eagle-import") (part "GQM2195C2E3R9BB12D"))
    )
    (comp (ref "C102")
      (value "GQM2195C2E2R7CB12D")
      (footprint "eagle-import:CAPC2012X100N")
      (fields (field (name "MOUSER_PART_NUMBER") "81-GQM2195C2E2R7CB2D"))
      (libsource (lib "eagle-import") (part "GQM2195C2E2R7CB12D"))
    )
    (comp (ref "C103")
      (value "GQM2195C2E2R7CB12D")
      (footprint "eagle-import:CAPC2012X100N")
      (fields (field (name "MOUSER_PART_NUMBER") "81-GQM2195C2E2R7CB2D"))
      (libsource (lib "eagle-import") (part "GQM2195C2E2R7CB12D"))
    )
    (comp (ref "C104")
      (value "GQM2195C2E5R6CB12D")
      (footprint "eagle-import:CAPC2012X100N")
      (fields (field (name "MOUSER_PART_NUMBER") "81-GQM2195C2E5R6CB2D"))
      (libsource (lib "eagle-import") (part "GQM2195C2E5R6CB12D"))
    )
    (comp (ref "C105")
      (value "GQM2195C2E6R8CB12D")
      (footprint "eagle-import:CAPC2012X100N")
      (fields (field (name "MOUSER_PART_NUMBER") "81-GQM2195C2E6R8CB2D"))
      (libsource (lib "eagle-import") (part "GQM2195C2E6R8CB12D"))
    )
    (comp (ref "C106")
      (value "GQM2195C2E3R9BB12D")
      (footprint "eagle-import:CAPC2012X100N")
      (libsource (lib "eagle-import") (part "GQM2195C2E3R9BB12D"))
    )
    (comp (ref "C107")
      (value "T491A226K010ATAUTO")
      (footprint "eagle-import:CAPPM3216X180N")
      (fields (field (name "MOUSER_PART_NUMBER") "80-T491A226K10ATAUTO"))
      (libsource (lib "eagle-import") (part "T491A226K010ATAUTO"))
    )
    (comp (ref "C108")
      (value "T491A226K010ATAUTO")
      (footprint "eagle-import:CAPPM3216X180N")
      (fields (field (name "MOUSER_PART_NUMBER") "80-T491A226K10ATAUTO"))
      (libsource (lib "eagle-import") (part "T491A226K010ATAUTO"))
    )
    (comp (ref "C109")
      (value "T491A226K010ATAUTO")
      (footprint "eagle-import:CAPPM3216X180N")
      (fields (field (name "MOUSER_PART_NUMBER") "80-T491A226K10ATAUTO"))
      (libsource (lib "eagle-import") (part "T491A226K010ATAUTO"))
    )
    (comp (ref "C110")
      (value "T491A226K010ATAUTO")
      (footprint "eagle-import:CAPPM3216X180N")
      (fields (field (name "MOUSER_PART_NUMBER") "80-T491A226K10ATAUTO"))
      (libsource (lib "eagle-import") (part "T491A226K010ATAUTO"))
    )
    (comp (ref "C111")
      (value "T489A106K010ATA2K2")
      (footprint "eagle-import:CAPPM3216X180N")
      (fields (field (name "MOUSER_PART_NUMBER") "80-T489A106K10ATA2K2"))
      (libsource (lib "eagle-import") (part "T489A106K010ATA2K2"))
    )
    (comp (ref "C112")
      (value "T489A106K010ATA2K2")
      (footprint "eagle-import:CAPPM3216X180N")
      (fields (field (name "MOUSER_PART_NUMBER") "80-T489A106K10ATA2K2"))
      (libsource (lib "eagle-import") (part "T489A106K010ATA2K2"))
    )
    (comp (ref "C113")
      (value "GRMMDXR60J105ME05D")
      (footprint "eagle-import:CAPC0502X28N")
      (fields (field (name "MOUSER_PART_NUMBER") "81-GRMMDXR60J105ME5D"))
      (libsource (lib "eagle-import") (part "GRMMDXR60J105ME05D"))
    )
    (comp (ref "C114")
      (value "GRMMDXR60J105ME05D")
      (footprint "eagle-import:CAPC0502X28N")
      (fields (field (name "MOUSER_PART_NUMBER") "81-GRMMDXR60J105ME5D"))
      (libsource (lib "eagle-import") (part "GRMMDXR60J105ME05D"))
    )
    (comp (ref "C115")
      (value "T491A226K010ATAUTO")
      (footprint "eagle-import:CAPPM3216X180N")
      (fields (field (name "MOUSER_PART_NUMBER") "80-T491A226K10ATAUTO"))
      (libsource (lib "eagle-import") (part "T491A226K010ATAUTO"))
    )
    (comp (ref "C116")
      (value "T489A106K010ATA2K2")
      (footprint "eagle-import:CAPPM3216X180N")
      (fields (field (name "MOUSER_PART_NUMBER") "80-T489A106K10ATA2K2"))
      (libsource (lib "eagle-import") (part "T489A106K010ATA2K2"))
    )
    (comp (ref "C117")
      (value "T489A106K010ATA2K2")
      (footprint "eagle-import:CAPPM3216X180N")
      (fields (field (name "MOUSER_PART_NUMBER") "80-T489A106K10ATA2K2"))
      (libsource (lib "eagle-import") (part "T489A106K010ATA2K2"))
    )
    (comp (ref "C118")
      (value "GRMMDXR60J105ME05D")
      (footprint "eagle-import:CAPC0502X28N")
      (fields (field (name "MOUSER_PART_NUMBER") "81-GRMMDXR60J105ME5D"))
      (libsource (lib "eagle-import") (part "GRMMDXR60J105ME05D"))
    )
    (comp (ref "C119")
      (value "GRMMDXR60J105ME05D")
      (footprint "eagle-import:CAPC0502X28N")
      (fields (field (name "MOUSER_PART_NUMBER") "81-GRMMDXR60J105ME5D"))
      (libsource (lib "eagle-import") (part "GRMMDXR60J105ME05D"))
    )
    (comp (ref "C120")
      (value "T491A226K010ATAUTO")
      (footprint "eagle-import:CAPPM3216X180N")
      (fields (field (name "MOUSER_PART_NUMBER") "80-T491A226K10ATAUTO"))
      (libsource (lib "eagle-import") (part "T491A226K010ATAUTO"))
    )
    (comp (ref "C121")
      (value "GQM2195C2E5R6CB12D")
      (footprint "eagle-import:CAPC2012X100N")
      (fields (field (name "MOUSER_PART_NUMBER") "81-GQM2195C2E5R6CB2D"))
      (libsource (lib "eagle-import") (part "GQM2195C2E5R6CB12D"))
    )
    (comp (ref "C122")
      (value "GQM2195C2E2R7CB12D")
      (footprint "eagle-import:CAPC2012X100N")
      (fields (field (name "MOUSER_PART_NUMBER") "81-GQM2195C2E2R7CB2D"))
      (libsource (lib "eagle-import") (part "GQM2195C2E2R7CB12D"))
    )
    (comp (ref "C123")
      (value "GQM2195C2E1R0BB12D")
      (footprint "eagle-import:CAPC2012X100N")
      (fields (field (name "MOUSER_PART_NUMBER") "81-GQM2195C2E1R0BB2D"))
      (libsource (lib "eagle-import") (part "GQM2195C2E1R0BB12D"))
    )
    (comp (ref "C124")
      (value "GQM2195C2E5R6CB12D")
      (footprint "eagle-import:CAPC2012X100N")
      (fields (field (name "MOUSER_PART_NUMBER") "81-GQM2195C2E5R6CB2D"))
      (libsource (lib "eagle-import") (part "GQM2195C2E5R6CB12D"))
    )
    (comp (ref "C125")
      (value "GQM2195C2E2R7CB12D")
      (footprint "eagle-import:CAPC2012X100N")
      (fields (field (name "MOUSER_PART_NUMBER") "81-GQM2195C2E2R7CB2D"))
      (libsource (lib "eagle-import") (part "GQM2195C2E2R7CB12D"))
    )
    (comp (ref "C126")
      (value "GQM2195C2E1R0BB12D")
      (footprint "eagle-import:CAPC2012X100N")
      (fields (field (name "MOUSER_PART_NUMBER") "81-GQM2195C2E1R0BB2D"))
      (libsource (lib "eagle-import") (part "GQM2195C2E1R0BB12D"))
    )
    (comp (ref "CLK_INPUT+")
      (value "BU-SMA-V")
      (footprint "eagle-import:BU-SMA-V")
      (libsource (lib "eagle-import") (part "con-coax_133_BU-SMA-V"))
    )
    (comp (ref "D1")
      (value "SMBJ5340B-TP")
      (footprint "eagle-import:DIOM5336X241N")
      (fields (field (name "MOUSER_PART_NUMBER") "833-SMBJ5340B-TP"))
      (libsource (lib "eagle-import") (part "SMBJ5340B-TP"))
    )
    (comp (ref "FERRITE_BEAD_1")
      (value "WE-CBF_0603(WB/HS)")
      (footprint "eagle-import:WE-CBF_0603(W=2.2)")
      (libsource (lib "eagle-import") (part "WE-CBF_0603(WB/HS)"))
    )
    (comp (ref "FERRITE_BEAD_2")
      (value "WE-CBF_0603(WB/HS)")
      (footprint "eagle-import:WE-CBF_0603(W=2.2)")
      (libsource (lib "eagle-import") (part "WE-CBF_0603(WB/HS)"))
    )
    (comp (ref "FERRITE_BEAD_3")
      (value "WE-CBF_0603(WB/HS)")
      (footprint "eagle-import:WE-CBF_0603(W=2.2)")
      (libsource (lib "eagle-import") (part "WE-CBF_0603(WB/HS)"))
    )
    (comp (ref "FERRITE_BEAD_4")
      (value "WE-CBF_0603(WB/HS)")
      (footprint "eagle-import:WE-CBF_0603(W=2.2)")
      (libsource (lib "eagle-import") (part "WE-CBF_0603(WB/HS)"))
    )
    (comp (ref "FERRITE_BEAD_5")
      (value "WE-CBF_0603(WB/HS)")
      (footprint "eagle-import:WE-CBF_0603(W=2.2)")
      (libsource (lib "eagle-import") (part "WE-CBF_0603(WB/HS)"))
    )
    (comp (ref "FERRITE_BEAD_6")
      (value "WE-CBF_0603(WB/HS)")
      (footprint "eagle-import:WE-CBF_0603(W=2.2)")
      (libsource (lib "eagle-import") (part "WE-CBF_0603(WB/HS)"))
    )
    (comp (ref "FERRITE_BEAD_7")
      (value "WE-CBF_0603(WB/HS)")
      (footprint "eagle-import:WE-CBF_0603(W=2.2)")
      (libsource (lib "eagle-import") (part "WE-CBF_0603(WB/HS)"))
    )
    (comp (ref "FERRITE_BEAD_8")
      (value "WE-CBF_0603(WB/HS)")
      (footprint "eagle-import:WE-CBF_0603(W=2.2)")
      (libsource (lib "eagle-import") (part "WE-CBF_0603(WB/HS)"))
    )
    (comp (ref "FERRITE_BEAD_9")
      (value "WE-CBF_0603(WB/HS)")
      (footprint "eagle-import:WE-CBF_0603(W=2.2)")
      (libsource (lib "eagle-import") (part "WE-CBF_0603(WB/HS)"))
    )
    (comp (ref "FERRITE_BEAD_10")
      (value "WE-CBF_0603(WB/HS)")
      (footprint "eagle-import:WE-CBF_0603(W=2.2)")
      (libsource (lib "eagle-import") (part "WE-CBF_0603(WB/HS)"))
    )
    (comp (ref "FERRITE_BEAD_11")
      (value "WE-CBF_0603(WB/HS)")
      (footprint "eagle-import:WE-CBF_0603(W=2.2)")
      (libsource (lib "eagle-import") (part "WE-CBF_0603(WB/HS)"))
    )
    (comp (ref "FERRITE_BEAD_12")
      (value "WE-CBF_0603(WB/HS)")
      (footprint "eagle-import:WE-CBF_0603(W=2.2)")
      (libsource (lib "eagle-import") (part "WE-CBF_0603(WB/HS)"))
    )
    (comp (ref "FILTERED_OUT")
      (value "BU-SMA-H")
      (footprint "eagle-import:BU-SMA-H")
      (libsource (lib "eagle-import") (part "BU-SMA-H"))
    )
    (comp (ref "FILTERED_OUT2")
      (value "BU-SMA-H")
      (footprint "eagle-import:BU-SMA-H")
      (libsource (lib "eagle-import") (part "BU-SMA-H"))
    )
    (comp (ref "J1")
      (value "KLDX-0202-AC")
      (footprint "eagle-import:KYCON_KLDX-0202-AC")
      (fields (field (name "MF") "Kycon"))
      (libsource (lib "eagle-import") (part "KLDX-0202-AC"))
    )
    (comp (ref "L1")
      (value "LQW2BAS18NJ00L")
      (footprint "eagle-import:LQW2BAN11NG00L")
      (fields (field (name "MOUSER_PART_NUMBER") "81-LQW2BAS18NJ00L"))
      (libsource (lib "eagle-import") (part "LQW2BAS18NJ00L"))
    )
    (comp (ref "L2")
      (value "LQW2BAS22NJ00L")
      (footprint "eagle-import:LQW2BAN11NG00L")
      (fields (field (name "MOUSER_PART_NUMBER") "81-LQW2BAS22NJ00L"))
      (libsource (lib "eagle-import") (part "LQW2BAS22NJ00L"))
    )
    (comp (ref "L3")
      (value "LQW2BAS27NJ00L")
      (footprint "eagle-import:LQW2BAN11NG00L")
      (fields (field (name "MOUSER_PART_NUMBER") "81-LQW2BAS27NJ00L"))
      (libsource (lib "eagle-import") (part "LQW2BAS27NJ00L"))
    )
    (comp (ref "L4")
      (value "LQW2BAS18NJ00L")
      (footprint "eagle-import:LQW2BAN11NG00L")
      (fields (field (name "MOUSER_PART_NUMBER") "81-LQW2BAS18NJ00L"))
      (libsource (lib "eagle-import") (part "LQW2BAS18NJ00L"))
    )
    (comp (ref "L5")
      (value "LQW2BAS22NJ00L")
      (footprint "eagle-import:LQW2BAN11NG00L")
      (fields (field (name "MOUSER_PART_NUMBER") "81-LQW2BAS22NJ00L"))
      (libsource (lib "eagle-import") (part "LQW2BAS22NJ00L"))
    )
    (comp (ref "L6")
      (value "LQW2BAS27NJ00L")
      (footprint "eagle-import:LQW2BAN11NG00L")
      (fields (field (name "MOUSER_PART_NUMBER") "81-LQW2BAS27NJ00L"))
      (libsource (lib "eagle-import") (part "LQW2BAS27NJ00L"))
    )
    (comp (ref "LED5")
      (value "SML-811UTT86C")
      (footprint "eagle-import:LEDC3412X115N")
      (fields (field (name "MOUSER_PART_NUMBER") "755-SML-811UTT86C"))
      (libsource (lib "eagle-import") (part "SML-811UTT86C"))
    )
    (comp (ref "PARALLEL1")
      (value "TSM-119-04-L-DV")
      (footprint "eagle-import:TSM-119-YY-ZZZ-DV")
      (libsource (lib "eagle-import") (part "TSM-119-04-L-DV"))
    )
    (comp (ref "PARALLEL2")
      (value "TSM-119-04-L-DV")
      (footprint "eagle-import:TSM-119-YY-ZZZ-DV")
      (libsource (lib "eagle-import") (part "TSM-119-04-L-DV"))
    )
    (comp (ref "PDCLK1")
      (value "BU-SMA-V")
      (footprint "eagle-import:BU-SMA-V")
      (libsource (lib "eagle-import") (part "BU-SMA-V"))
    )
    (comp (ref "PDCLK2")
      (value "BU-SMA-V")
      (footprint "eagle-import:BU-SMA-V")
      (libsource (lib "eagle-import") (part "BU-SMA-V"))
    )
    (comp (ref "PROFILE")
      (value "M20-8760842P")
      (footprint "eagle-import:M208760842P")
      (fields (field (name "MOUSER_PART_NUMBER") "855-M20-8760842P"))
      (libsource (lib "eagle-import") (part "M20-8760842P"))
    )
    (comp (ref "PS1")
      (value "ADP-2-10")
      (footprint "eagle-import:CD636")
      (libsource (lib "eagle-import") (part "ADP-2-10"))
    )
    (comp (ref "PWR_DWN")
      (value "67996-106HLF")
      (footprint "eagle-import:HDRV6W67P254_2X3_762X483X858P")
      (fields (field (name "MOUSER_PART_NUMBER") "649-67996-106HLF"))
      (libsource (lib "eagle-import") (part "67996-106HLF"))
    )
    (comp (ref "R1")
      (value "TNPW020150R0BEED")
      (footprint "eagle-import:RESC0603X26N")
      (fields (field (name "MOUSER_PART_NUMBER") "71-TNPW020150R0BEED"))
      (libsource (lib "eagle-import") (part "TNPW020150R0BEED"))
    )
    (comp (ref "R6")
      (value "TNPU040210K0AYEP00")
      (footprint "eagle-import:RESC1005X40N")
      (fields (field (name "MOUSER_PART_NUMBER") "71-TNPU040210K0AYEP0"))
      (libsource (lib "eagle-import") (part "TNPU040210K0AYEP00"))
    )
    (comp (ref "R7")
      (value "TNPW020150R0BEED")
      (footprint "eagle-import:RESC0603X26N")
      (fields (field (name "MOUSER_PART_NUMBER") "71-TNPW020150R0BEED"))
      (libsource (lib "eagle-import") (part "TNPW020150R0BEED"))
    )
    (comp (ref "R13")
      (value "TNPW020150R0BEED")
      (footprint "eagle-import:RESC0603X26N")
      (fields (field (name "MOUSER_PART_NUMBER") "71-TNPW020150R0BEED"))
      (libsource (lib "eagle-import") (part "TNPW020150R0BEED"))
    )
    (comp (ref "R14")
      (value "TNPW020150R0BEED")
      (footprint "eagle-import:RESC0603X26N")
      (fields (field (name "MOUSER_PART_NUMBER") "71-TNPW020150R0BEED"))
      (libsource (lib "eagle-import") (part "TNPW020150R0BEED"))
    )
    (comp (ref "R15")
      (value "CRCW020124R9FNED")
      (footprint "eagle-import:RESC0603X28N")
      (fields (field (name "MOUSER_PART_NUMBER") "71-CRCW020124R9FNED"))
      (libsource (lib "eagle-import") (part "CRCW020124R9FNED"))
    )
    (comp (ref "R16")
      (value "CRCW020124R9FNED")
      (footprint "eagle-import:RESC0603X28N")
      (fields (field (name "MOUSER_PART_NUMBER") "71-CRCW020124R9FNED"))
      (libsource (lib "eagle-import") (part "CRCW020124R9FNED"))
    )
    (comp (ref "R17")
      (value "TNPU040210K0AYEP00")
      (footprint "eagle-import:RESC1005X40N")
      (fields (field (name "MOUSER_PART_NUMBER") "71-TNPU040210K0AYEP0"))
      (libsource (lib "eagle-import") (part "TNPU040210K0AYEP00"))
    )
    (comp (ref "R27")
      (value "300")
      (footprint "eagle-import:RES_ERA3VEB3000V")
      (fields (field (name "MF") "Panasonic") (field (name "MP") "ERA-3VEB3000V"))
      (libsource (lib "eagle-import") (part "ERA3VEB3000V"))
    )
    (comp (ref "R29")
      (value "CRCW0402100RFKEDC")
      (footprint "eagle-import:RESC1005X35N")
      (fields (field (name "MOUSER_PART_NUMBER") "71-CRCW0402100RFKEDC"))
      (libsource (lib "eagle-import") (part "CRCW0402100RFKEDC"))
    )
    (comp (ref "R36")
      (value "CRCW0402100RFKEDC")
      (footprint "eagle-import:RESC1005X35N")
      (fields (field (name "MOUSER_PART_NUMBER") "71-CRCW0402100RFKEDC"))
      (libsource (lib "eagle-import") (part "CRCW0402100RFKEDC"))
    )
    (comp (ref "R41")
      (value "CRCW020124R9FNED")
      (footprint "eagle-import:RESC0603X28N")
      (fields (field (name "MOUSER_PART_NUMBER") "71-CRCW020124R9FNED"))
      (libsource (lib "eagle-import") (part "CRCW020124R9FNED"))
    )
    (comp (ref "R42")
      (value "CRCW020124R9FNED")
      (footprint "eagle-import:RESC0603X28N")
      (fields (field (name "MOUSER_PART_NUMBER") "71-CRCW020124R9FNED"))
      (libsource (lib "eagle-import") (part "CRCW020124R9FNED"))
    )
    (comp (ref "RAMP1")
      (value "M20-8760342R")
      (footprint "eagle-import:M208760342R")
      (fields (field (name "MOUSER_PART_NUMBER") "855-M20-8760342R"))
      (libsource (lib "eagle-import") (part "M20-8760342R"))
    )
    (comp (ref "RAMP2")
      (value "M20-8760342R")
      (footprint "eagle-import:M208760342R")
      (fields (field (name "MOUSER_PART_NUMBER") "855-M20-8760342R"))
      (libsource (lib "eagle-import") (part "M20-8760342R"))
    )
    (comp (ref "REG1")
      (value "AZ1117CH-1.8TRG1")
      (footprint "eagle-import:SOT230P700X180-4N")
      (fields (field (name "MOUSER_PART_NUMBER") "621-AZ1117CH-1.8TRG1"))
      (libsource (lib "eagle-import") (part "AZ1117CH-1.8TRG1"))
    )
    (comp (ref "REG2")
      (value "AZ1117CH-1.8TRG1")
      (footprint "eagle-import:SOT230P700X180-4N")
      (fields (field (name "MOUSER_PART_NUMBER") "621-AZ1117CH-1.8TRG1"))
      (libsource (lib "eagle-import") (part "AZ1117CH-1.8TRG1"))
    )
    (comp (ref "REG3")
      (value "TPS7B8333QDCYRQ1")
      (footprint "eagle-import:SOT230P700X180-4N")
      (fields (field (name "MOUSER_PART_NUMBER") "595-TPS7B8333QDCYRQ1"))
      (libsource (lib "eagle-import") (part "TPS7B8333QDCYRQ1"))
    )
    (comp (ref "REG4")
      (value "AZ1117CH-1.8TRG1")
      (footprint "eagle-import:SOT230P700X180-4N")
      (fields (field (name "MOUSER_PART_NUMBER") "621-AZ1117CH-1.8TRG1"))
      (libsource (lib "eagle-import") (part "AZ1117CH-1.8TRG1"))
    )
    (comp (ref "REG5")
      (value "TPS7B8333QDCYRQ1")
      (footprint "eagle-import:SOT230P700X180-4N")
      (fields (field (name "MOUSER_PART_NUMBER") "595-TPS7B8333QDCYRQ1"))
      (libsource (lib "eagle-import") (part "TPS7B8333QDCYRQ1"))
    )
    (comp (ref "REG6")
      (value "AZ1117CH-1.8TRG1")
      (footprint "eagle-import:SOT230P700X180-4N")
      (fields (field (name "MOUSER_PART_NUMBER") "621-AZ1117CH-1.8TRG1"))
      (libsource (lib "eagle-import") (part "AZ1117CH-1.8TRG1"))
    )
    (comp (ref "REG7")
      (value "AZ1117CH-1.8TRG1")
      (footprint "eagle-import:SOT230P700X180-4N")
      (fields (field (name "MOUSER_PART_NUMBER") "621-AZ1117CH-1.8TRG1"))
      (libsource (lib "eagle-import") (part "AZ1117CH-1.8TRG1"))
    )
    (comp (ref "REG8")
      (value "AZ1117CH-1.8TRG1")
      (footprint "eagle-import:SOT230P700X180-4N")
      (fields (field (name "MOUSER_PART_NUMBER") "621-AZ1117CH-1.8TRG1"))
      (libsource (lib "eagle-import") (part "AZ1117CH-1.8TRG1"))
    )
    (comp (ref "REG9")
      (value "TPS7B8333QDCYRQ1")
      (footprint "eagle-import:SOT230P700X180-4N")
      (fields (field (name "MOUSER_PART_NUMBER") "595-TPS7B8333QDCYRQ1"))
      (libsource (lib "eagle-import") (part "TPS7B8333QDCYRQ1"))
    )
    (comp (ref "REG10")
      (value "AZ1117CH-1.8TRG1")
      (footprint "eagle-import:SOT230P700X180-4N")
      (fields (field (name "MOUSER_PART_NUMBER") "621-AZ1117CH-1.8TRG1"))
      (libsource (lib "eagle-import") (part "AZ1117CH-1.8TRG1"))
    )
    (comp (ref "REG11")
      (value "TPS7B8333QDCYRQ1")
      (footprint "eagle-import:SOT230P700X180-4N")
      (fields (field (name "MOUSER_PART_NUMBER") "595-TPS7B8333QDCYRQ1"))
      (libsource (lib "eagle-import") (part "TPS7B8333QDCYRQ1"))
    )
    (comp (ref "REG12")
      (value "AZ1117CH-1.8TRG1")
      (footprint "eagle-import:SOT230P700X180-4N")
      (fields (field (name "MOUSER_PART_NUMBER") "621-AZ1117CH-1.8TRG1"))
      (libsource (lib "eagle-import") (part "AZ1117CH-1.8TRG1"))
    )
    (comp (ref "SPI_CTRL")
      (value "M20-8760842P")
      (footprint "eagle-import:M208760842P")
      (fields (field (name "MOUSER_PART_NUMBER") "855-M20-8760842P"))
      (libsource (lib "eagle-import") (part "M20-8760842P"))
    )
    (comp (ref "SW1")
      (value "100SP1T2B4M6QE")
      (footprint "eagle-import:TOGGLE_RA")
      (fields (field (name "MF") "E-Switch"))
      (libsource (lib "eagle-import") (part "100SP1T2B4M6QE"))
    )
    (comp (ref "SYNC_CLK1")
      (value "BU-SMA-V")
      (footprint "eagle-import:BU-SMA-V")
      (libsource (lib "eagle-import") (part "BU-SMA-V"))
    )
    (comp (ref "SYNC_CLK2")
      (value "BU-SMA-V")
      (footprint "eagle-import:BU-SMA-V")
      (libsource (lib "eagle-import") (part "BU-SMA-V"))
    )
    (comp (ref "SYNC_IN+1")
      (value "BU-SMA-V")
      (footprint "eagle-import:BU-SMA-V")
      (libsource (lib "eagle-import") (part "BU-SMA-V"))
    )
    (comp (ref "SYNC_IN+2")
      (value "BU-SMA-V")
      (footprint "eagle-import:BU-SMA-V")
      (libsource (lib "eagle-import") (part "BU-SMA-V"))
    )
    (comp (ref "SYNC_IN-1")
      (value "BU-SMA-V")
      (footprint "eagle-import:BU-SMA-V")
      (libsource (lib "eagle-import") (part "BU-SMA-V"))
    )
    (comp (ref "SYNC_IN-2")
      (value "BU-SMA-V")
      (footprint "eagle-import:BU-SMA-V")
      (libsource (lib "eagle-import") (part "BU-SMA-V"))
    )
    (comp (ref "SYNC_OUT+1")
      (value "BU-SMA-V")
      (footprint "eagle-import:BU-SMA-V")
      (libsource (lib "eagle-import") (part "BU-SMA-V"))
    )
    (comp (ref "SYNC_OUT+2")
      (value "BU-SMA-V")
      (footprint "eagle-import:BU-SMA-V")
      (libsource (lib "eagle-import") (part "BU-SMA-V"))
    )
    (comp (ref "SYNC_OUT-1")
      (value "BU-SMA-V")
      (footprint "eagle-import:BU-SMA-V")
      (libsource (lib "eagle-import") (part "BU-SMA-V"))
    )
    (comp (ref "SYNC_OUT-2")
      (value "BU-SMA-V")
      (footprint "eagle-import:BU-SMA-V")
      (libsource (lib "eagle-import") (part "BU-SMA-V"))
    )
    (comp (ref "T1")
      (value "TC2-72T+")
      (footprint "eagle-import:AT1521_MNC")
      (fields (field (name "COPYRIGHT") "Copyright (C) 2022 Ultra Librarian. All rights reserved."))
      (libsource (lib "eagle-import") (part "TC2-72T+"))
    )
    (comp (ref "T2")
      (value "ETC1-1-13TR")
      (footprint "eagle-import:SM22")
      (fields (field (name "MF") "M/A-Com Technology"))
      (libsource (lib "eagle-import") (part "ETC1-1-13TR"))
    )
    (comp (ref "T3")
      (value "ETC1-1-13TR")
      (footprint "eagle-import:SM22")
      (fields (field (name "MF") "M/A-Com Technology"))
      (libsource (lib "eagle-import") (part "ETC1-1-13TR"))
    )
    (comp (ref "T4")
      (value "TC2-72T+")
      (footprint "eagle-import:AT1521_MNC")
      (fields (field (name "COPYRIGHT") "Copyright (C) 2022 Ultra Librarian. All rights reserved."))
      (libsource (lib "eagle-import") (part "TC2-72T+"))
    )
    (comp (ref "TP1")
      (value "TPPAD1-13")
      (footprint "eagle-import:P1-13")
      (libsource (lib "eagle-import") (part "TPPAD1-13"))
    )
    (comp (ref "TP2")
      (value "TPPAD1-13")
      (footprint "eagle-import:P1-13")
      (libsource (lib "eagle-import") (part "TPPAD1-13"))
    )
    (comp (ref "TP3")
      (value "TPPAD1-13")
      (footprint "eagle-import:P1-13")
      (libsource (lib "eagle-import") (part "TPPAD1-13"))
    )
    (comp (ref "TP4")
      (value "TPPAD1-13")
      (footprint "eagle-import:P1-13")
      (libsource (lib "eagle-import") (part "TPPAD1-13"))
    )
    (comp (ref "TP5")
      (value "TPPAD1-13")
      (footprint "eagle-import:P1-13")
      (libsource (lib "eagle-import") (part "TPPAD1-13"))
    )
    (comp (ref "TP6")
      (value "TPPAD1-13")
      (footprint "eagle-import:P1-13")
      (libsource (lib "eagle-import") (part "TPPAD1-13"))
    )
    (comp (ref "TP7")
      (value "TPPAD1-13")
      (footprint "eagle-import:P1-13")
      (libsource (lib "eagle-import") (part "TPPAD1-13"))
    )
    (comp (ref "TP8")
      (value "TPPAD1-13")
      (footprint "eagle-import:P1-13")
      (libsource (lib "eagle-import") (part "TPPAD1-13"))
    )
    (comp (ref "TP9")
      (value "TPPAD1-13")
      (footprint "eagle-import:P1-13")
      (libsource (lib "eagle-import") (part "TPPAD1-13"))
    )
    (comp (ref "TP10")
      (value "TPPAD1-13")
      (footprint "eagle-import:P1-13")
      (libsource (lib "eagle-import") (part "TPPAD1-13"))
    )
    (comp (ref "U1")
      (value "AD9910BSVZ")
      (footprint "eagle-import:QFP50P1600X1600X120-101N")
      (fields (field (name "MF") "Analog Devices"))
      (libsource (lib "eagle-import") (part "AD9910BSVZ"))
    )
    (comp (ref "U2")
      (value "AD9910BSVZ")
      (footprint "eagle-import:QFP50P1600X1600X120-101N")
      (fields (field (name "MF") "Analog Devices"))
      (libsource (lib "eagle-import") (part "AD9910BSVZ"))
    )
  )
  (nets
    (net (code "1") (name "/CKV1") (class "Default")
      (node (ref "C10") (pin "1") (pinfunction "+_1") (pintype "bidirectional"))
      (node (ref "C11") (pin "1") (pinfunction "1_1") (pintype "bidirectional"))
      (node (ref "FERRITE_BEAD_1") (pin "1") (pinfunction "1_1") (pintype "passive"))
      (node (ref "REG1") (pin "2") (pinfunction "OUTPUT_2") (pintype "bidirectional"))
      (node (ref "REG1") (pin "4") (pinfunction "VOUT_4") (pintype "bidirectional"))
    )
    (net (code "2") (name "/CKV2") (class "Default")
      (node (ref "C23") (pin "1") (pinfunction "+_1") (pintype "bidirectional"))
      (node (ref "C24") (pin "1") (pinfunction "1_1") (pintype "bidirectional"))
      (node (ref "FERRITE_BEAD_2") (pin "1") (pinfunction "1_1") (pintype "passive"))
      (node (ref "REG2") (pin "2") (pinfunction "OUTPUT_2") (pintype "bidirectional"))
      (node (ref "REG2") (pin "4") (pinfunction "VOUT_4") (pintype "bidirectional"))
    )
    (net (code "3") (name "/CKV3") (class "Default")
      (node (ref "C43") (pin "1") (pinfunction "1_1") (pintype "bidirectional"))
      (node (ref "C45") (pin "1") (pinfunction "+_1") (pintype "bidirectional"))
      (node (ref "FERRITE_BEAD_6") (pin "1") (pinfunction "1_1") (pintype "passive"))
      (node (ref "REG6") (pin "2") (pinfunction "OUTPUT_2") (pintype "bidirectional"))
      (node (ref "REG6") (pin "4") (pinfunction "VOUT_4") (pintype "bidirectional"))
    )
    (net (code "4") (name "/CLK4") (class "Default")
      (node (ref "C107") (pin "1") (pinfunction "+_1") (pintype "bidirectional"))
      (node (ref "C62") (pin "1") (pinfunction "1_1") (pintype "bidirectional"))
      (node (ref "FERRITE_BEAD_7") (pin "1") (pinfunction "1_1") (pintype "passive"))
      (node (ref "REG7") (pin "2") (pinfunction "OUTPUT_2") (pintype "bidirectional"))
      (node (ref "REG7") (pin "4") (pinfunction "VOUT_4") (pintype "bidirectional"))
    )
    (net (code "5") (name "/CLK5") (class "Default")
      (node (ref "C108") (pin "1") (pinfunction "+_1") (pintype "bidirectional"))
      (node (ref "C60") (pin "1") (pinfunction "1_1") (pintype "bidirectional"))
      (node (ref "FERRITE_BEAD_8") (pin "1") (pinfunction "1_1") (pintype "passive"))
      (node (ref "REG8") (pin "2") (pinfunction "OUTPUT_2") (pintype "bidirectional"))
      (node (ref "REG8") (pin "4") (pinfunction "VOUT_4") (pintype "bidirectional"))
    )
    (net (code "6") (name "/CLK6") (class "Default")
      (node (ref "C118") (pin "1") (pinfunction "1_1") (pintype "bidirectional"))
      (node (ref "C120") (pin "1") (pinfunction "+_1") (pintype "bidirectional"))
      (node (ref "FERRITE_BEAD_12") (pin "1") (pinfunction "1_1") (pintype "passive"))
      (node (ref "REG12") (pin "2") (pinfunction "OUTPUT_2") (pintype "bidirectional"))
      (node (ref "REG12") (pin "4") (pinfunction "VOUT_4") (pintype "bidirectional"))
    )
    (net (code "7") (name "/CLK_IN") (class "Default")
      (node (ref "CLK_INPUT+") (pin "1") (pinfunction "1_1") (pintype "passive"))
      (node (ref "PS1") (pin "1") (pinfunction "SUM_1") (pintype "bidirectional"))
    )
    (net (code "8") (name "/DAC1") (class "Default")
      (node (ref "C19") (pin "1") (pinfunction "1_1") (pintype "bidirectional"))
      (node (ref "C37") (pin "1") (pinfunction "+_1") (pintype "bidirectional"))
      (node (ref "FERRITE_BEAD_5") (pin "1") (pinfunction "1_1") (pintype "passive"))
      (node (ref "REG5") (pin "3") (pinfunction "OUT_3") (pintype "bidirectional"))
    )
    (net (code "9") (name "/DAC2") (class "Default")
      (node (ref "C113") (pin "1") (pinfunction "1_1") (pintype "bidirectional"))
      (node (ref "C115") (pin "1") (pinfunction "+_1") (pintype "bidirectional"))
      (node (ref "FERRITE_BEAD_11") (pin "1") (pinfunction "1_1") (pintype "passive"))
      (node (ref "REG11") (pin "3") (pinfunction "OUT_3") (pintype "bidirectional"))
    )
    (net (code "10") (name "/DAC_RSET") (class "Default")
      (node (ref "R6") (pin "1") (pinfunction "1_1") (pintype "bidirectional"))
      (node (ref "U1") (pin "84") (pinfunction "DAC_RSET_84") (pintype "output"))
    )
    (net (code "11") (name "/DAC_RSET2") (class "Default")
      (node (ref "R17") (pin "1") (pinfunction "1_1") (pintype "bidirectional"))
      (node (ref "U2") (pin "84") (pinfunction "DAC_RSET_84") (pintype "output"))
    )
    (net (code "12") (name "/DVDD1.8V1") (class "Default")
      (node (ref "C40") (pin "1") (pinfunction "+_1") (pintype "bidirectional"))
      (node (ref "C41") (pin "1") (pinfunction "1_1") (pintype "bidirectional"))
      (node (ref "FERRITE_BEAD_4") (pin "1") (pinfunction "1_1") (pintype "passive"))
      (node (ref "REG4") (pin "2") (pinfunction "OUTPUT_2") (pintype "bidirectional"))
      (node (ref "REG4") (pin "4") (pinfunction "VOUT_4") (pintype "bidirectional"))
    )
    (net (code "13") (name "/DVDD1.8V2") (class "Default")
      (node (ref "C110") (pin "1") (pinfunction "+_1") (pintype "bidirectional"))
      (node (ref "C50") (pin "1") (pinfunction "1_1") (pintype "bidirectional"))
      (node (ref "FERRITE_BEAD_10") (pin "1") (pinfunction "1_1") (pintype "passive"))
      (node (ref "REG10") (pin "2") (pinfunction "OUTPUT_2") (pintype "bidirectional"))
      (node (ref "REG10") (pin "4") (pinfunction "VOUT_4") (pintype "bidirectional"))
    )
    (net (code "14") (name "/DVDD3.3V1") (class "Default")
      (node (ref "C35") (pin "1") (pinfunction "+_1") (pintype "bidirectional"))
      (node (ref "C36") (pin "1") (pinfunction "1_1") (pintype "bidirectional"))
      (node (ref "FERRITE_BEAD_3") (pin "1") (pinfunction "1_1") (pintype "passive"))
      (node (ref "REG3") (pin "3") (pinfunction "OUT_3") (pintype "bidirectional"))
    )
    (net (code "15") (name "/DVDD3.3V2") (class "Default")
      (node (ref "C109") (pin "1") (pinfunction "+_1") (pintype "bidirectional"))
      (node (ref "C58") (pin "1") (pinfunction "1_1") (pintype "bidirectional"))
      (node (ref "FERRITE_BEAD_9") (pin "1") (pinfunction "1_1") (pintype "passive"))
      (node (ref "REG9") (pin "3") (pinfunction "OUT_3") (pintype "bidirectional"))
    )
    (net (code "16") (name "/PDCLK") (class "Default")
      (node (ref "PDCLK1") (pin "1") (pinfunction "1_1") (pintype "passive"))
      (node (ref "U1") (pin "40") (pinfunction "PDCLK_40") (pintype "output"))
    )
    (net (code "17") (name "/PDCLK2") (class "Default")
      (node (ref "PDCLK2") (pin "1") (pinfunction "1_1") (pintype "passive"))
      (node (ref "U2") (pin "40") (pinfunction "PDCLK_40") (pintype "output"))
    )
    (net (code "18") (name "/SYNC_CLK") (class "Default")
      (node (ref "SYNC_CLK1") (pin "1") (pinfunction "1_1") (pintype "passive"))
      (node (ref "U1") (pin "55") (pinfunction "SYNC_CLK_55") (pintype "output"))
    )
    (net (code "19") (name "/SYNC_CLK2") (class "Default")
      (node (ref "SYNC_CLK2") (pin "1") (pinfunction "1_1") (pintype "passive"))
      (node (ref "U2") (pin "55") (pinfunction "SYNC_CLK_55") (pintype "output"))
    )
    (net (code "20") (name "CLK_VDD_1") (class "Default")
      (node (ref "C29") (pin "1") (pinfunction "+_1") (pintype "bidirectional"))
      (node (ref "C68") (pin "1") (pinfunction "1_1") (pintype "passive"))
      (node (ref "C82") (pin "1") (pinfunction "1_1") (pintype "bidirectional"))
      (node (ref "FERRITE_BEAD_1") (pin "2") (pinfunction "2_2") (pintype "passive"))
      (node (ref "U1") (pin "3") (pinfunction "AVDD_(1.8V)_3") (pintype "power_in"))
    )
    (net (code "21") (name "CLK_VDD_2") (class "Default")
      (node (ref "C33") (pin "1") (pinfunction "+_1") (pintype "bidirectional"))
      (node (ref "C69") (pin "1") (pinfunction "1_1") (pintype "passive"))
      (node (ref "C74") (pin "1") (pinfunction "1_1") (pintype "bidirectional"))
      (node (ref "FERRITE_BEAD_2") (pin "2") (pinfunction "2_2") (pintype "passive"))
      (node (ref "U1") (pin "6") (pinfunction "AVDD_(1.8V)_2_6") (pintype "power_in"))
    )
    (net (code "22") (name "CLK_VDD_3") (class "Default")
      (node (ref "C20") (pin "1") (pinfunction "1_1") (pintype "passive"))
      (node (ref "C38") (pin "1") (pinfunction "+_1") (pintype "bidirectional"))
      (node (ref "C44") (pin "1") (pinfunction "1_1") (pintype "bidirectional"))
      (node (ref "C81") (pin "1") (pinfunction "1_1") (pintype "passive"))
      (node (ref "FERRITE_BEAD_6") (pin "2") (pinfunction "2_2") (pintype "passive"))
      (node (ref "U1") (pin "89") (pinfunction "AVDD_(1.8V)_3_89") (pintype "power_in"))
      (node (ref "U1") (pin "92") (pinfunction "AVDD_(1.8V)_4_92") (pintype "power_in"))
    )
    (net (code "23") (name "CLK_VDD_4") (class "Default")
      (node (ref "C21") (pin "1") (pinfunction "+_1") (pintype "bidirectional"))
      (node (ref "C63") (pin "1") (pinfunction "1_1") (pintype "bidirectional"))
      (node (ref "C93") (pin "1") (pinfunction "1_1") (pintype "passive"))
      (node (ref "FERRITE_BEAD_7") (pin "2") (pinfunction "2_2") (pintype "passive"))
      (node (ref "U2") (pin "3") (pinfunction "AVDD_(1.8V)_3") (pintype "power_in"))
    )
    (net (code "24") (name "CLK_VDD_5") (class "Default")
      (node (ref "C15") (pin "1") (pinfunction "+_1") (pintype "bidirectional"))
      (node (ref "C61") (pin "1") (pinfunction "1_1") (pintype "bidirectional"))
      (node (ref "C94") (pin "1") (pinfunction "1_1") (pintype "passive"))
      (node (ref "FERRITE_BEAD_8") (pin "2") (pinfunction "2_2") (pintype "passive"))
      (node (ref "U2") (pin "6") (pinfunction "AVDD_(1.8V)_2_6") (pintype "power_in"))
    )
    (net (code "25") (name "CLK_VDD_6") (class "Default")
      (node (ref "C116") (pin "1") (pinfunction "+_1") (pintype "bidirectional"))
      (node (ref "C119") (pin "1") (pinfunction "1_1") (pintype "bidirectional"))
      (node (ref "C95") (pin "1") (pinfunction "1_1") (pintype "passive"))
      (node (ref "C96") (pin "1") (pinfunction "1_1") (pintype "passive"))
      (node (ref "FERRITE_BEAD_12") (pin "2") (pinfunction "2_2") (pintype "passive"))
      (node (ref "U2") (pin "89") (pinfunction "AVDD_(1.8V)_3_89") (pintype "power_in"))
      (node (ref "U2") (pin "92") (pinfunction "AVDD_(1.8V)_4_92") (pintype "power_in"))
    )
    (net (code "26") (name "CS*") (class "Default")
      (node (ref "SPI_CTRL") (pin "8") (pinfunction "8_8") (pintype "bidirectional"))
      (node (ref "U1") (pin "70") (pinfunction "CS*_70") (pintype "input"))
    )
    (net (code "27") (name "CS*2") (class "Default")
      (node (ref "SPI_CTRL") (pin "10") (pinfunction "10_10") (pintype "bidirectional"))
      (node (ref "U2") (pin "70") (pinfunction "CS*_70") (pintype "input"))
    )
    (net (code "28") (name "D0-1") (class "Default")
      (node (ref "PARALLEL1") (pin "34") (pinfunction "34_34") (pintype "bidirectional"))
      (node (ref "U1") (pin "48") (pinfunction "D0_48") (pintype "input"))
    )
    (net (code "29") (name "D0-2") (class "Default")
      (node (ref "PARALLEL2") (pin "34") (pinfunction "34_34") (pintype "bidirectional"))
      (node (ref "U2") (pin "48") (pinfunction "D0_48") (pintype "input"))
    )
    (net (code "30") (name "D1-1") (class "Default")
      (node (ref "PARALLEL1") (pin "32") (pinfunction "32_32") (pintype "bidirectional"))
      (node (ref "U1") (pin "44") (pinfunction "D1_44") (pintype "input"))
    )
    (net (code "31") (name "D1-2") (class "Default")
      (node (ref "PARALLEL2") (pin "32") (pinfunction "32_32") (pintype "bidirectional"))
      (node (ref "U2") (pin "44") (pinfunction "D1_44") (pintype "input"))
    )
    (net (code "32") (name "D2-1") (class "Default")
      (node (ref "PARALLEL1") (pin "30") (pinfunction "30_30") (pintype "bidirectional"))
      (node (ref "U1") (pin "43") (pinfunction "D2_43") (pintype "input"))
    )
    (net (code "33") (name "D2-2") (class "Default")
      (node (ref "PARALLEL2") (pin "30") (pinfunction "30_30") (pintype "bidirectional"))
      (node (ref "U2") (pin "43") (pinfunction "D2_43") (pintype "input"))
    )
    (net (code "34") (name "D3-1") (class "Default")
      (node (ref "PARALLEL1") (pin "28") (pinfunction "28_28") (pintype "bidirectional"))
      (node (ref "U1") (pin "42") (pinfunction "D3_42") (pintype "input"))
    )
    (net (code "35") (name "D3-2") (class "Default")
      (node (ref "PARALLEL2") (pin "28") (pinfunction "28_28") (pintype "bidirectional"))
      (node (ref "U2") (pin "42") (pinfunction "D3_42") (pintype "input"))
    )
    (net (code "36") (name "D4-1") (class "Default")
      (node (ref "PARALLEL1") (pin "24") (pinfunction "24_24") (pintype "bidirectional"))
      (node (ref "U1") (pin "39") (pinfunction "D4_39") (pintype "input"))
    )
    (net (code "37") (name "D4-2") (class "Default")
      (node (ref "PARALLEL2") (pin "24") (pinfunction "24_24") (pintype "bidirectional"))
      (node (ref "U2") (pin "39") (pinfunction "D4_39") (pintype "input"))
    )
    (net (code "38") (name "D5-1") (class "Default")
      (node (ref "PARALLEL1") (pin "22") (pinfunction "22_22") (pintype "bidirectional"))
      (node (ref "U1") (pin "38") (pinfunction "D5_38") (pintype "input"))
    )
    (net (code "39") (name "D5-2") (class "Default")
      (node (ref "PARALLEL2") (pin "22") (pinfunction "22_22") (pintype "bidirectional"))
      (node (ref "U2") (pin "38") (pinfunction "D5_38") (pintype "input"))
    )
    (net (code "40") (name "D6-1") (class "Default")
      (node (ref "PARALLEL1") (pin "20") (pinfunction "20_20") (pintype "bidirectional"))
      (node (ref "U1") (pin "37") (pinfunction "D6_37") (pintype "input"))
    )
    (net (code "41") (name "D6-2") (class "Default")
      (node (ref "PARALLEL2") (pin "20") (pinfunction "20_20") (pintype "bidirectional"))
      (node (ref "U2") (pin "37") (pinfunction "D6_37") (pintype "input"))
    )
    (net (code "42") (name "D7-1") (class "Default")
      (node (ref "PARALLEL1") (pin "18") (pinfunction "18_18") (pintype "bidirectional"))
      (node (ref "U1") (pin "36") (pinfunction "D7_36") (pintype "input"))
    )
    (net (code "43") (name "D7-2") (class "Default")
      (node (ref "PARALLEL2") (pin "18") (pinfunction "18_18") (pintype "bidirectional"))
      (node (ref "U2") (pin "36") (pinfunction "D7_36") (pintype "input"))
    )
    (net (code "44") (name "D8-1") (class "Default")
      (node (ref "PARALLEL1") (pin "16") (pinfunction "16_16") (pintype "bidirectional"))
      (node (ref "U1") (pin "35") (pinfunction "D8_35") (pintype "input"))
    )
    (net (code "45") (name "D8-2") (class "Default")
      (node (ref "PARALLEL2") (pin "16") (pinfunction "16_16") (pintype "bidirectional"))
      (node (ref "U2") (pin "35") (pinfunction "D8_35") (pintype "input"))
    )
    (net (code "46") (name "D9-1") (class "Default")
      (node (ref "PARALLEL1") (pin "14") (pinfunction "14_14") (pintype "bidirectional"))
      (node (ref "U1") (pin "34") (pinfunction "D9_34") (pintype "input"))
    )
    (net (code "47") (name "D9-2") (class "Default")
      (node (ref "PARALLEL2") (pin "14") (pinfunction "14_14") (pintype "bidirectional"))
      (node (ref "U2") (pin "34") (pinfunction "D9_34") (pintype "input"))
    )
    (net (code "48") (name "D10-1") (class "Default")
      (node (ref "PARALLEL1") (pin "12") (pinfunction "12_12") (pintype "bidirectional"))
      (node (ref "U1") (pin "33") (pinfunction "D10_33") (pintype "input"))
    )
    (net (code "49") (name "D10-2") (class "Default")
      (node (ref "PARALLEL2") (pin "12") (pinfunction "12_12") (pintype "bidirectional"))
      (node (ref "U2") (pin "33") (pinfunction "D10_33") (pintype "input"))
    )
    (net (code "50") (name "D11-1") (class "Default")
      (node (ref "PARALLEL1") (pin "10") (pinfunction "10_10") (pintype "bidirectional"))
      (node (ref "U1") (pin "32") (pinfunction "D11_32") (pintype "input"))
    )
    (net (code "51") (name "D11-2") (class "Default")
      (node (ref "PARALLEL2") (pin "10") (pinfunction "10_10") (pintype "bidirectional"))
      (node (ref "U2") (pin "32") (pinfunction "D11_32") (pintype "input"))
    )
    (net (code "52") (name "D12-1") (class "Default")
      (node (ref "PARALLEL1") (pin "8") (pinfunction "8_8") (pintype "bidirectional"))
      (node (ref "U1") (pin "31") (pinfunction "D12_31") (pintype "input"))
    )
    (net (code "53") (name "D12-2") (class "Default")
      (node (ref "PARALLEL2") (pin "8") (pinfunction "8_8") (pintype "bidirectional"))
      (node (ref "U2") (pin "31") (pinfunction "D12_31") (pintype "input"))
    )
    (net (code "54") (name "D13-1") (class "Default")
      (node (ref "PARALLEL1") (pin "6") (pinfunction "6_6") (pintype "bidirectional"))
      (node (ref "U1") (pin "27") (pinfunction "D13_27") (pintype "input"))
    )
    (net (code "55") (name "D13-2") (class "Default")
      (node (ref "PARALLEL2") (pin "6") (pinfunction "6_6") (pintype "bidirectional"))
      (node (ref "U2") (pin "27") (pinfunction "D13_27") (pintype "input"))
    )
    (net (code "56") (name "D14-1") (class "Default")
      (node (ref "PARALLEL1") (pin "4") (pinfunction "4_4") (pintype "bidirectional"))
      (node (ref "U1") (pin "26") (pinfunction "D14_26") (pintype "input"))
    )
    (net (code "57") (name "D14-2") (class "Default")
      (node (ref "PARALLEL2") (pin "4") (pinfunction "4_4") (pintype "bidirectional"))
      (node (ref "U2") (pin "26") (pinfunction "D14_26") (pintype "input"))
    )
    (net (code "58") (name "D15-1") (class "Default")
      (node (ref "PARALLEL1") (pin "2") (pinfunction "2_2") (pintype "bidirectional"))
      (node (ref "U1") (pin "25") (pinfunction "D15_25") (pintype "input"))
    )
    (net (code "59") (name "D15-2") (class "Default")
      (node (ref "PARALLEL2") (pin "2") (pinfunction "2_2") (pintype "bidirectional"))
      (node (ref "U2") (pin "25") (pinfunction "D15_25") (pintype "input"))
    )
    (net (code "60") (name "DAC_VDD") (class "Default")
      (node (ref "C12") (pin "1") (pinfunction "+_1") (pintype "bidirectional"))
      (node (ref "C32") (pin "1") (pinfunction "1_1") (pintype "bidirectional"))
      (node (ref "C70") (pin "1") (pinfunction "1_1") (pintype "passive"))
      (node (ref "C71") (pin "1") (pinfunction "1_1") (pintype "passive"))
      (node (ref "C72") (pin "1") (pinfunction "1_1") (pintype "passive"))
      (node (ref "FERRITE_BEAD_5") (pin "2") (pinfunction "2_2") (pintype "passive"))
      (node (ref "U1") (pin "74") (pinfunction "AVDD_(3.3V)_2_74") (pintype "power_in"))
      (node (ref "U1") (pin "75") (pinfunction "AVDD_(3.3V)_75") (pintype "power_in"))
      (node (ref "U1") (pin "76") (pinfunction "AVDD_(3.3V)_3_76") (pintype "power_in"))
      (node (ref "U1") (pin "77") (pinfunction "AVDD_(3.3V)_4_77") (pintype "power_in"))
      (node (ref "U1") (pin "83") (pinfunction "AVDD_(3.3V)_5_83") (pintype "power_in"))
    )
    (net (code "61") (name "DAC_VDD2") (class "Default")
      (node (ref "C111") (pin "1") (pinfunction "+_1") (pintype "bidirectional"))
      (node (ref "C114") (pin "1") (pinfunction "1_1") (pintype "bidirectional"))
      (node (ref "C84") (pin "1") (pinfunction "1_1") (pintype "passive"))
      (node (ref "C85") (pin "1") (pinfunction "1_1") (pintype "passive"))
      (node (ref "C86") (pin "1") (pinfunction "1_1") (pintype "passive"))
      (node (ref "FERRITE_BEAD_11") (pin "2") (pinfunction "2_2") (pintype "passive"))
      (node (ref "U2") (pin "74") (pinfunction "AVDD_(3.3V)_2_74") (pintype "power_in"))
      (node (ref "U2") (pin "75") (pinfunction "AVDD_(3.3V)_75") (pintype "power_in"))
      (node (ref "U2") (pin "76") (pinfunction "AVDD_(3.3V)_3_76") (pintype "power_in"))
      (node (ref "U2") (pin "77") (pinfunction "AVDD_(3.3V)_4_77") (pintype "power_in"))
      (node (ref "U2") (pin "83") (pinfunction "AVDD_(3.3V)_5_83") (pintype "power_in"))
    )
    (net (code "62") (name "DRCTL1") (class "Default")
      (node (ref "RAMP1") (pin "4") (pinfunction "4_4") (pintype "bidirectional"))
      (node (ref "U1") (pin "62") (pinfunction "DRCTL_62") (pintype "input"))
    )
    (net (code "63") (name "DRCTL2") (class "Default")
      (node (ref "RAMP2") (pin "4") (pinfunction "4_4") (pintype "bidirectional"))
      (node (ref "U2") (pin "62") (pinfunction "DRCTL_62") (pintype "input"))
    )
    (net (code "64") (name "DRHOLD1") (class "Default")
      (node (ref "RAMP1") (pin "6") (pinfunction "6_6") (pintype "bidirectional"))
      (node (ref "U1") (pin "63") (pinfunction "DRHOLD_63") (pintype "input"))
    )
    (net (code "65") (name "DRHOLD2") (class "Default")
      (node (ref "RAMP2") (pin "6") (pinfunction "6_6") (pintype "bidirectional"))
      (node (ref "U2") (pin "63") (pinfunction "DRHOLD_63") (pintype "input"))
    )
    (net (code "66") (name "DROVER") (class "Default")
      (node (ref "TP5") (pin "TP") (pinfunction "TP_TP") (pintype "input"))
      (node (ref "U1") (pin "61") (pinfunction "DROVER_61") (pintype "output"))
    )
    (net (code "67") (name "DROVER2") (class "Default")
      (node (ref "TP8") (pin "TP") (pinfunction "TP_TP") (pintype "input"))
      (node (ref "U2") (pin "61") (pinfunction "DROVER_61") (pintype "output"))
    )
    (net (code "68") (name "DVDD(1.8V)") (class "Default")
      (node (ref "C14") (pin "1") (pinfunction "1_1") (pintype "passive"))
      (node (ref "C16") (pin "1") (pinfunction "1_1") (pintype "passive"))
      (node (ref "C17") (pin "1") (pinfunction "1_1") (pintype "passive"))
      (node (ref "C30") (pin "1") (pinfunction "+_1") (pintype "bidirectional"))
      (node (ref "C65") (pin "1") (pinfunction "1_1") (pintype "passive"))
      (node (ref "C66") (pin "1") (pinfunction "1_1") (pintype "passive"))
      (node (ref "C67") (pin "1") (pinfunction "1_1") (pintype "passive"))
      (node (ref "C75") (pin "1") (pinfunction "1_1") (pintype "bidirectional"))
      (node (ref "FERRITE_BEAD_4") (pin "2") (pinfunction "2_2") (pintype "passive"))
      (node (ref "U1") (pin "17") (pinfunction "DVDD_(1.8V)_2_17") (pintype "power_in"))
      (node (ref "U1") (pin "23") (pinfunction "DVDD_(1.8V)_4_23") (pintype "power_in"))
      (node (ref "U1") (pin "30") (pinfunction "DVDD_(1.8V)_3_30") (pintype "power_in"))
      (node (ref "U1") (pin "47") (pinfunction "DVDD_(1.8V)_5_47") (pintype "power_in"))
      (node (ref "U1") (pin "57") (pinfunction "DVDD_(1.8V)_57") (pintype "power_in"))
      (node (ref "U1") (pin "64") (pinfunction "DVDD_(1.8V)_6_64") (pintype "power_in"))
    )
    (net (code "69") (name "DVDD2(1.8V)") (class "Default")
      (node (ref "C1") (pin "1") (pinfunction "+_1") (pintype "bidirectional"))
      (node (ref "C57") (pin "1") (pinfunction "1_1") (pintype "bidirectional"))
      (node (ref "C87") (pin "1") (pinfunction "1_1") (pintype "passive"))
      (node (ref "C88") (pin "1") (pinfunction "1_1") (pintype "passive"))
      (node (ref "C89") (pin "1") (pinfunction "1_1") (pintype "passive"))
      (node (ref "C90") (pin "1") (pinfunction "1_1") (pintype "passive"))
      (node (ref "C91") (pin "1") (pinfunction "1_1") (pintype "passive"))
      (node (ref "C92") (pin "1") (pinfunction "1_1") (pintype "passive"))
      (node (ref "FERRITE_BEAD_10") (pin "2") (pinfunction "2_2") (pintype "passive"))
      (node (ref "U2") (pin "17") (pinfunction "DVDD_(1.8V)_2_17") (pintype "power_in"))
      (node (ref "U2") (pin "23") (pinfunction "DVDD_(1.8V)_4_23") (pintype "power_in"))
      (node (ref "U2") (pin "30") (pinfunction "DVDD_(1.8V)_3_30") (pintype "power_in"))
      (node (ref "U2") (pin "47") (pinfunction "DVDD_(1.8V)_5_47") (pintype "power_in"))
      (node (ref "U2") (pin "57") (pinfunction "DVDD_(1.8V)_57") (pintype "power_in"))
      (node (ref "U2") (pin "64") (pinfunction "DVDD_(1.8V)_6_64") (pintype "power_in"))
    )
    (net (code "70") (name "DVDD_I{slash}O(3.3V)") (class "Default")
      (node (ref "C2") (pin "1") (pinfunction "1_1") (pintype "passive"))
      (node (ref "C3") (pin "1") (pinfunction "1_1") (pintype "passive"))
      (node (ref "C31") (pin "1") (pinfunction "+_1") (pintype "bidirectional"))
      (node (ref "C4") (pin "1") (pinfunction "1_1") (pintype "passive"))
      (node (ref "C5") (pin "1") (pinfunction "1_1") (pintype "passive"))
      (node (ref "C6") (pin "1") (pinfunction "1_1") (pintype "passive"))
      (node (ref "C7") (pin "1") (pinfunction "1_1") (pintype "passive"))
      (node (ref "C76") (pin "1") (pinfunction "1_1") (pintype "bidirectional"))
      (node (ref "C8") (pin "1") (pinfunction "1_1") (pintype "passive"))
      (node (ref "FERRITE_BEAD_3") (pin "2") (pinfunction "2_2") (pintype "passive"))
      (node (ref "U1") (pin "11") (pinfunction "DVDD_I/O_(3.3V)_11") (pintype "power_in"))
      (node (ref "U1") (pin "15") (pinfunction "DVDD_I/O_(3.3V)_2_15") (pintype "power_in"))
      (node (ref "U1") (pin "21") (pinfunction "DVDD_I/O_(3.3V)_3_21") (pintype "power_in"))
      (node (ref "U1") (pin "28") (pinfunction "DVDD_I/O_(3.3V)_7_28") (pintype "power_in"))
      (node (ref "U1") (pin "45") (pinfunction "DVDD_I/O_(3.3V)_4_45") (pintype "power_in"))
      (node (ref "U1") (pin "56") (pinfunction "DVDD_I/O_(3.3V)_5_56") (pintype "power_in"))
      (node (ref "U1") (pin "66") (pinfunction "DVDD_I/O_(3.3V)_6_66") (pintype "power_in"))
    )
    (net (code "71") (name "DVDD_I{slash}O2(3.3V)") (class "Default")
      (node (ref "C13") (pin "1") (pinfunction "+_1") (pintype "bidirectional"))
      (node (ref "C59") (pin "1") (pinfunction "1_1") (pintype "bidirectional"))
      (node (ref "C64") (pin "1") (pinfunction "1_1") (pintype "passive"))
      (node (ref "C73") (pin "1") (pinfunction "1_1") (pintype "passive"))
      (node (ref "C77") (pin "1") (pinfunction "1_1") (pintype "passive"))
      (node (ref "C78") (pin "1") (pinfunction "1_1") (pintype "passive"))
      (node (ref "C79") (pin "1") (pinfunction "1_1") (pintype "passive"))
      (node (ref "C80") (pin "1") (pinfunction "1_1") (pintype "passive"))
      (node (ref "C83") (pin "1") (pinfunction "1_1") (pintype "passive"))
      (node (ref "FERRITE_BEAD_9") (pin "2") (pinfunction "2_2") (pintype "passive"))
      (node (ref "PWR_DWN") (pin "5") (pinfunction "5_5") (pintype "bidirectional"))
      (node (ref "PWR_DWN") (pin "6") (pinfunction "6_6") (pintype "bidirectional"))
      (node (ref "U2") (pin "11") (pinfunction "DVDD_I/O_(3.3V)_11") (pintype "power_in"))
      (node (ref "U2") (pin "15") (pinfunction "DVDD_I/O_(3.3V)_2_15") (pintype "power_in"))
      (node (ref "U2") (pin "21") (pinfunction "DVDD_I/O_(3.3V)_3_21") (pintype "power_in"))
      (node (ref "U2") (pin "28") (pinfunction "DVDD_I/O_(3.3V)_7_28") (pintype "power_in"))
      (node (ref "U2") (pin "45") (pinfunction "DVDD_I/O_(3.3V)_4_45") (pintype "power_in"))
      (node (ref "U2") (pin "56") (pinfunction "DVDD_I/O_(3.3V)_5_56") (pintype "power_in"))
      (node (ref "U2") (pin "66") (pinfunction "DVDD_I/O_(3.3V)_6_66") (pintype "power_in"))
    )
    (net (code "72") (name "EXT_PWR_DWN") (class "Default")
      (node (ref "PWR_DWN") (pin "4") (pinfunction "4_4") (pintype "bidirectional"))
      (node (ref "U1") (pin "18") (pinfunction "EXT_PWR_DWN_18") (pintype "input"))
    )
    (net (code "73") (name "EXT_PWR_DWN2") (class "Default")
      (node (ref "PWR_DWN") (pin "3") (pinfunction "3_3") (pintype "bidirectional"))
      (node (ref "U2") (pin "18") (pinfunction "EXT_PWR_DWN_18") (pintype "input"))
    )
    (net (code "74") (name "F0-1") (class "Default")
      (node (ref "PARALLEL1") (pin "38") (pinfunction "38_38") (pintype "bidirectional"))
      (node (ref "U1") (pin "50") (pinfunction "F0_50") (pintype "input"))
    )
    (net (code "75") (name "F0-2") (class "Default")
      (node (ref "PARALLEL2") (pin "38") (pinfunction "38_38") (pintype "bidirectional"))
      (node (ref "U2") (pin "50") (pinfunction "F0_50") (pintype "input"))
    )
    (net (code "76") (name "F1-1") (class "Default")
      (node (ref "PARALLEL1") (pin "36") (pinfunction "36_36") (pintype "bidirectional"))
      (node (ref "U1") (pin "49") (pinfunction "F1_49") (pintype "input"))
    )
    (net (code "77") (name "F1-2") (class "Default")
      (node (ref "PARALLEL2") (pin "36") (pinfunction "36_36") (pintype "bidirectional"))
      (node (ref "U2") (pin "49") (pinfunction "F1_49") (pintype "input"))
    )
    (net (code "78") (name "GND") (class "Default")
      (node (ref "C1") (pin "2") (pinfunction "-_2") (pintype "bidirectional"))
      (node (ref "C10") (pin "2") (pinfunction "-_2") (pintype "bidirectional"))
      (node (ref "C100") (pin "2") (pinfunction "2_2") (pintype "bidirectional"))
      (node (ref "C101") (pin "2") (pinfunction "2_2") (pintype "bidirectional"))
      (node (ref "C102") (pin "2") (pinfunction "2_2") (pintype "bidirectional"))
      (node (ref "C103") (pin "2") (pinfunction "2_2") (pintype "bidirectional"))
      (node (ref "C104") (pin "2") (pinfunction "2_2") (pintype "bidirectional"))
      (node (ref "C105") (pin "2") (pinfunction "2_2") (pintype "bidirectional"))
      (node (ref "C106") (pin "2") (pinfunction "2_2") (pintype "bidirectional"))
      (node (ref "C107") (pin "2") (pinfunction "-_2") (pintype "bidirectional"))
      (node (ref "C108") (pin "2") (pinfunction "-_2") (pintype "bidirectional"))
      (node (ref "C109") (pin "2") (pinfunction "-_2") (pintype "bidirectional"))
      (node (ref "C11") (pin "2") (pinfunction "2_2") (pintype "bidirectional"))
      (node (ref "C110") (pin "2") (pinfunction "-_2") (pintype "bidirectional"))
      (node (ref "C111") (pin "2") (pinfunction "-_2") (pintype "bidirectional"))
      (node (ref "C112") (pin "2") (pinfunction "-_2") (pintype "bidirectional"))
      (node (ref "C113") (pin "2") (pinfunction "2_2") (pintype "bidirectional"))
      (node (ref "C114") (pin "2") (pinfunction "2_2") (pintype "bidirectional"))
      (node (ref "C115") (pin "2") (pinfunction "-_2") (pintype "bidirectional"))
      (node (ref "C116") (pin "2") (pinfunction "-_2") (pintype "bidirectional"))
      (node (ref "C117") (pin "2") (pinfunction "-_2") (pintype "bidirectional"))
      (node (ref "C118") (pin "2") (pinfunction "2_2") (pintype "bidirectional"))
      (node (ref "C119") (pin "2") (pinfunction "2_2") (pintype "bidirectional"))
      (node (ref "C12") (pin "2") (pinfunction "-_2") (pintype "bidirectional"))
      (node (ref "C120") (pin "2") (pinfunction "-_2") (pintype "bidirectional"))
      (node (ref "C13") (pin "2") (pinfunction "-_2") (pintype "bidirectional"))
      (node (ref "C14") (pin "2") (pinfunction "2_2") (pintype "passive"))
      (node (ref "C15") (pin "2") (pinfunction "-_2") (pintype "bidirectional"))
      (node (ref "C16") (pin "2") (pinfunction "2_2") (pintype "passive"))
      (node (ref "C17") (pin "2") (pinfunction "2_2") (pintype "passive"))
      (node (ref "C18") (pin "2") (pinfunction "-_2") (pintype "bidirectional"))
      (node (ref "C19") (pin "2") (pinfunction "2_2") (pintype "bidirectional"))
      (node (ref "C2") (pin "2") (pinfunction "2_2") (pintype "passive"))
      (node (ref "C20") (pin "2") (pinfunction "2_2") (pintype "passive"))
      (node (ref "C21") (pin "2") (pinfunction "-_2") (pintype "bidirectional"))
      (node (ref "C22") (pin "2") (pinfunction "-_2") (pintype "bidirectional"))
      (node (ref "C23") (pin "2") (pinfunction "-_2") (pintype "bidirectional"))
      (node (ref "C24") (pin "2") (pinfunction "2_2") (pintype "bidirectional"))
      (node (ref "C25") (pin "2") (pinfunction "2_2") (pintype "bidirectional"))
      (node (ref "C26") (pin "2") (pinfunction "2_2") (pintype "bidirectional"))
      (node (ref "C27") (pin "2") (pinfunction "2_2") (pintype "bidirectional"))
      (node (ref "C28") (pin "2") (pinfunction "2_2") (pintype "bidirectional"))
      (node (ref "C29") (pin "2") (pinfunction "-_2") (pintype "bidirectional"))
      (node (ref "C3") (pin "2") (pinfunction "2_2") (pintype "passive"))
      (node (ref "C30") (pin "2") (pinfunction "-_2") (pintype "bidirectional"))
      (node (ref "C31") (pin "2") (pinfunction "-_2") (pintype "bidirectional"))
      (node (ref "C32") (pin "2") (pinfunction "2_2") (pintype "bidirectional"))
      (node (ref "C33") (pin "2") (pinfunction "-_2") (pintype "bidirectional"))
      (node (ref "C34") (pin "2") (pinfunction "-_2") (pintype "bidirectional"))
      (node (ref "C35") (pin "2") (pinfunction "-_2") (pintype "bidirectional"))
      (node (ref "C36") (pin "2") (pinfunction "2_2") (pintype "bidirectional"))
      (node (ref "C37") (pin "2") (pinfunction "-_2") (pintype "bidirectional"))
      (node (ref "C38") (pin "2") (pinfunction "-_2") (pintype "bidirectional"))
      (node (ref "C39") (pin "2") (pinfunction "-_2") (pintype "bidirectional"))
      (node (ref "C4") (pin "2") (pinfunction "2_2") (pintype "passive"))
      (node (ref "C40") (pin "2") (pinfunction "-_2") (pintype "bidirectional"))
      (node (ref "C41") (pin "2") (pinfunction "2_2") (pintype "bidirectional"))
      (node (ref "C42") (pin "2") (pinfunction "-_2") (pintype "bidirectional"))
      (node (ref "C43") (pin "2") (pinfunction "2_2") (pintype "bidirectional"))
      (node (ref "C44") (pin "2") (pinfunction "2_2") (pintype "bidirectional"))
      (node (ref "C45") (pin "2") (pinfunction "-_2") (pintype "bidirectional"))
      (node (ref "C46") (pin "2") (pinfunction "-_2") (pintype "bidirectional"))
      (node (ref "C47") (pin "2") (pinfunction "-_2") (pintype "bidirectional"))
      (node (ref "C48") (pin "2") (pinfunction "-_2") (pintype "bidirectional"))
      (node (ref "C49") (pin "2") (pinfunction "-_2") (pintype "bidirectional"))
      (node (ref "C5") (pin "2") (pinfunction "2_2") (pintype "passive"))
      (node (ref "C50") (pin "2") (pinfunction "2_2") (pintype "bidirectional"))
      (node (ref "C53") (pin "2") (pinfunction "2_2") (pintype "bidirectional"))
      (node (ref "C54") (pin "2") (pinfunction "2_2") (pintype "bidirectional"))
      (node (ref "C55") (pin "2") (pinfunction "2_2") (pintype "bidirectional"))
      (node (ref "C56") (pin "2") (pinfunction "2_2") (pintype "bidirectional"))
      (node (ref "C57") (pin "2") (pinfunction "2_2") (pintype "bidirectional"))
      (node (ref "C58") (pin "2") (pinfunction "2_2") (pintype "bidirectional"))
      (node (ref "C59") (pin "2") (pinfunction "2_2") (pintype "bidirectional"))
      (node (ref "C6") (pin "2") (pinfunction "2_2") (pintype "passive"))
      (node (ref "C60") (pin "2") (pinfunction "2_2") (pintype "bidirectional"))
      (node (ref "C61") (pin "2") (pinfunction "2_2") (pintype "bidirectional"))
      (node (ref "C62") (pin "2") (pinfunction "2_2") (pintype "bidirectional"))
      (node (ref "C63") (pin "2") (pinfunction "2_2") (pintype "bidirectional"))
      (node (ref "C64") (pin "2") (pinfunction "2_2") (pintype "passive"))
      (node (ref "C65") (pin "2") (pinfunction "2_2") (pintype "passive"))
      (node (ref "C66") (pin "2") (pinfunction "2_2") (pintype "passive"))
      (node (ref "C67") (pin "2") (pinfunction "2_2") (pintype "passive"))
      (node (ref "C68") (pin "2") (pinfunction "2_2") (pintype "passive"))
      (node (ref "C69") (pin "2") (pinfunction "2_2") (pintype "passive"))
      (node (ref "C7") (pin "2") (pinfunction "2_2") (pintype "passive"))
      (node (ref "C70") (pin "2") (pinfunction "2_2") (pintype "passive"))
      (node (ref "C71") (pin "2") (pinfunction "2_2") (pintype "passive"))
      (node (ref "C72") (pin "2") (pinfunction "2_2") (pintype "passive"))
      (node (ref "C73") (pin "2") (pinfunction "2_2") (pintype "passive"))
      (node (ref "C74") (pin "2") (pinfunction "2_2") (pintype "bidirectional"))
      (node (ref "C75") (pin "2") (pinfunction "2_2") (pintype "bidirectional"))
      (node (ref "C76") (pin "2") (pinfunction "2_2") (pintype "bidirectional"))
      (node (ref "C77") (pin "2") (pinfunction "2_2") (pintype "passive"))
      (node (ref "C78") (pin "2") (pinfunction "2_2") (pintype "passive"))
      (node (ref "C79") (pin "2") (pinfunction "2_2") (pintype "passive"))
      (node (ref "C8") (pin "2") (pinfunction "2_2") (pintype "passive"))
      (node (ref "C80") (pin "2") (pinfunction "2_2") (pintype "passive"))
      (node (ref "C81") (pin "2") (pinfunction "2_2") (pintype "passive"))
      (node (ref "C82") (pin "2") (pinfunction "2_2") (pintype "bidirectional"))
      (node (ref "C83") (pin "2") (pinfunction "2_2") (pintype "passive"))
      (node (ref "C84") (pin "2") (pinfunction "2_2") (pintype "passive"))
      (node (ref "C85") (pin "2") (pinfunction "2_2") (pintype "passive"))
      (node (ref "C86") (pin "2") (pinfunction "2_2") (pintype "passive"))
      (node (ref "C87") (pin "2") (pinfunction "2_2") (pintype "passive"))
      (node (ref "C88") (pin "2") (pinfunction "2_2") (pintype "passive"))
      (node (ref "C89") (pin "2") (pinfunction "2_2") (pintype "passive"))
      (node (ref "C9") (pin "2") (pinfunction "-_2") (pintype "bidirectional"))
      (node (ref "C90") (pin "2") (pinfunction "2_2") (pintype "passive"))
      (node (ref "C91") (pin "2") (pinfunction "2_2") (pintype "passive"))
      (node (ref "C92") (pin "2") (pinfunction "2_2") (pintype "passive"))
      (node (ref "C93") (pin "2") (pinfunction "2_2") (pintype "passive"))
      (node (ref "C94") (pin "2") (pinfunction "2_2") (pintype "passive"))
      (node (ref "C95") (pin "2") (pinfunction "2_2") (pintype "passive"))
      (node (ref "C96") (pin "2") (pinfunction "2_2") (pintype "passive"))
      (node (ref "C99") (pin "2") (pinfunction "2_2") (pintype "bidirectional"))
      (node (ref "CLK_INPUT+") (pin "2") (pinfunction "2_2") (pintype "passive"))
      (node (ref "CLK_INPUT+") (pin "3") (pinfunction "2_3") (pintype "passive"))
      (node (ref "CLK_INPUT+") (pin "4") (pinfunction "2_4") (pintype "passive"))
      (node (ref "CLK_INPUT+") (pin "5") (pinfunction "2_5") (pintype "passive"))
      (node (ref "D1") (pin "2") (pinfunction "A_2") (pintype "power_in"))
      (node (ref "FILTERED_OUT") (pin "2") (pinfunction "2_2") (pintype "passive"))
      (node (ref "FILTERED_OUT") (pin "3") (pinfunction "2_3") (pintype "passive"))
      (node (ref "FILTERED_OUT") (pin "4") (pinfunction "2_4") (pintype "passive"))
      (node (ref "FILTERED_OUT") (pin "5") (pinfunction "2_5") (pintype "passive"))
      (node (ref "FILTERED_OUT2") (pin "2") (pinfunction "2_2") (pintype "passive"))
      (node (ref "FILTERED_OUT2") (pin "3") (pinfunction "2_3") (pintype "passive"))
      (node (ref "FILTERED_OUT2") (pin "4") (pinfunction "2_4") (pintype "passive"))
      (node (ref "FILTERED_OUT2") (pin "5") (pinfunction "2_5") (pintype "passive"))
      (node (ref "J1") (pin "2") (pinfunction "2_2") (pintype "passive"))
      (node (ref "J1") (pin "3") (pinfunction "3_3") (pintype "passive"))
      (node (ref "PARALLEL1") (pin "1") (pinfunction "1_1") (pintype "bidirectional"))
      (node (ref "PARALLEL1") (pin "11") (pinfunction "11_11") (pintype "bidirectional"))
      (node (ref "PARALLEL1") (pin "13") (pinfunction "13_13") (pintype "bidirectional"))
      (node (ref "PARALLEL1") (pin "15") (pinfunction "15_15") (pintype "bidirectional"))
      (node (ref "PARALLEL1") (pin "17") (pinfunction "17_17") (pintype "bidirectional"))
      (node (ref "PARALLEL1") (pin "19") (pinfunction "19_19") (pintype "bidirectional"))
      (node (ref "PARALLEL1") (pin "21") (pinfunction "21_21") (pintype "bidirectional"))
      (node (ref "PARALLEL1") (pin "23") (pinfunction "23_23") (pintype "bidirectional"))
      (node (ref "PARALLEL1") (pin "25") (pinfunction "25_25") (pintype "bidirectional"))
      (node (ref "PARALLEL1") (pin "27") (pinfunction "27_27") (pintype "bidirectional"))
      (node (ref "PARALLEL1") (pin "29") (pinfunction "29_29") (pintype "bidirectional"))
      (node (ref "PARALLEL1") (pin "3") (pinfunction "3_3") (pintype "bidirectional"))
      (node (ref "PARALLEL1") (pin "31") (pinfunction "31_31") (pintype "bidirectional"))
      (node (ref "PARALLEL1") (pin "33") (pinfunction "33_33") (pintype "bidirectional"))
      (node (ref "PARALLEL1") (pin "35") (pinfunction "35_35") (pintype "bidirectional"))
      (node (ref "PARALLEL1") (pin "37") (pinfunction "37_37") (pintype "bidirectional"))
      (node (ref "PARALLEL1") (pin "5") (pinfunction "5_5") (pintype "bidirectional"))
      (node (ref "PARALLEL1") (pin "7") (pinfunction "7_7") (pintype "bidirectional"))
      (node (ref "PARALLEL1") (pin "9") (pinfunction "9_9") (pintype "bidirectional"))
      (node (ref "PARALLEL2") (pin "1") (pinfunction "1_1") (pintype "bidirectional"))
      (node (ref "PARALLEL2") (pin "11") (pinfunction "11_11") (pintype "bidirectional"))
      (node (ref "PARALLEL2") (pin "13") (pinfunction "13_13") (pintype "bidirectional"))
      (node (ref "PARALLEL2") (pin "15") (pinfunction "15_15") (pintype "bidirectional"))
      (node (ref "PARALLEL2") (pin "17") (pinfunction "17_17") (pintype "bidirectional"))
      (node (ref "PARALLEL2") (pin "19") (pinfunction "19_19") (pintype "bidirectional"))
      (node (ref "PARALLEL2") (pin "21") (pinfunction "21_21") (pintype "bidirectional"))
      (node (ref "PARALLEL2") (pin "23") (pinfunction "23_23") (pintype "bidirectional"))
      (node (ref "PARALLEL2") (pin "25") (pinfunction "25_25") (pintype "bidirectional"))
      (node (ref "PARALLEL2") (pin "27") (pinfunction "27_27") (pintype "bidirectional"))
      (node (ref "PARALLEL2") (pin "29") (pinfunction "29_29") (pintype "bidirectional"))
      (node (ref "PARALLEL2") (pin "3") (pinfunction "3_3") (pintype "bidirectional"))
      (node (ref "PARALLEL2") (pin "31") (pinfunction "31_31") (pintype "bidirectional"))
      (node (ref "PARALLEL2") (pin "33") (pinfunction "33_33") (pintype "bidirectional"))
      (node (ref "PARALLEL2") (pin "35") (pinfunction "35_35") (pintype "bidirectional"))
      (node (ref "PARALLEL2") (pin "37") (pinfunction "37_37") (pintype "bidirectional"))
      (node (ref "PARALLEL2") (pin "5") (pinfunction "5_5") (pintype "bidirectional"))
      (node (ref "PARALLEL2") (pin "7") (pinfunction "7_7") (pintype "bidirectional"))
      (node (ref "PARALLEL2") (pin "9") (pinfunction "9_9") (pintype "bidirectional"))
      (node (ref "PDCLK1") (pin "2") (pinfunction "2_2") (pintype "passive"))
      (node (ref "PDCLK1") (pin "3") (pinfunction "2_3") (pintype "passive"))
      (node (ref "PDCLK1") (pin "4") (pinfunction "2_4") (pintype "passive"))
      (node (ref "PDCLK1") (pin "5") (pinfunction "2_5") (pintype "passive"))
      (node (ref "PDCLK2") (pin "2") (pinfunction "2_2") (pintype "passive"))
      (node (ref "PDCLK2") (pin "3") (pinfunction "2_3") (pintype "passive"))
      (node (ref "PDCLK2") (pin "4") (pinfunction "2_4") (pintype "passive"))
      (node (ref "PDCLK2") (pin "5") (pinfunction "2_5") (pintype "passive"))
      (node (ref "PROFILE") (pin "1") (pinfunction "1_1") (pintype "bidirectional"))
      (node (ref "PROFILE") (pin "11") (pinfunction "11_11") (pintype "bidirectional"))
      (node (ref "PROFILE") (pin "13") (pinfunction "13_13") (pintype "bidirectional"))
      (node (ref "PROFILE") (pin "15") (pinfunction "15_15") (pintype "bidirectional"))
      (node (ref "PROFILE") (pin "3") (pinfunction "3_3") (pintype "bidirectional"))
      (node (ref "PROFILE") (pin "5") (pinfunction "5_5") (pintype "bidirectional"))
      (node (ref "PROFILE") (pin "7") (pinfunction "7_7") (pintype "bidirectional"))
      (node (ref "PROFILE") (pin "9") (pinfunction "9_9") (pintype "bidirectional"))
      (node (ref "PWR_DWN") (pin "1") (pinfunction "1_1") (pintype "bidirectional"))
      (node (ref "PWR_DWN") (pin "2") (pinfunction "2_2") (pintype "bidirectional"))
      (node (ref "R1") (pin "2") (pinfunction "2_2") (pintype "bidirectional"))
      (node (ref "R13") (pin "2") (pinfunction "2_2") (pintype "bidirectional"))
      (node (ref "R14") (pin "1") (pinfunction "1_1") (pintype "bidirectional"))
      (node (ref "R15") (pin "1") (pinfunction "1_1") (pintype "bidirectional"))
      (node (ref "R16") (pin "1") (pinfunction "1_1") (pintype "bidirectional"))
      (node (ref "R17") (pin "2") (pinfunction "2_2") (pintype "bidirectional"))
      (node (ref "R27") (pin "1") (pinfunction "1_1") (pintype "passive"))
      (node (ref "R41") (pin "1") (pinfunction "1_1") (pintype "bidirectional"))
      (node (ref "R42") (pin "1") (pinfunction "1_1") (pintype "bidirectional"))
      (node (ref "R6") (pin "2") (pinfunction "2_2") (pintype "bidirectional"))
      (node (ref "R7") (pin "1") (pinfunction "1_1") (pintype "bidirectional"))
      (node (ref "RAMP1") (pin "1") (pinfunction "1_1") (pintype "bidirectional"))
      (node (ref "RAMP1") (pin "3") (pinfunction "3_3") (pintype "bidirectional"))
      (node (ref "RAMP1") (pin "5") (pinfunction "5_5") (pintype "bidirectional"))
      (node (ref "RAMP2") (pin "1") (pinfunction "1_1") (pintype "bidirectional"))
      (node (ref "RAMP2") (pin "3") (pinfunction "3_3") (pintype "bidirectional"))
      (node (ref "RAMP2") (pin "5") (pinfunction "5_5") (pintype "bidirectional"))
      (node (ref "REG1") (pin "1") (pinfunction "ADJ/GND_1") (pintype "bidirectional"))
      (node (ref "REG10") (pin "1") (pinfunction "ADJ/GND_1") (pintype "bidirectional"))
      (node (ref "REG11") (pin "2") (pinfunction "GND_1_2") (pintype "bidirectional"))
      (node (ref "REG11") (pin "4") (pinfunction "GND_2_4") (pintype "bidirectional"))
      (node (ref "REG12") (pin "1") (pinfunction "ADJ/GND_1") (pintype "bidirectional"))
      (node (ref "REG2") (pin "1") (pinfunction "ADJ/GND_1") (pintype "bidirectional"))
      (node (ref "REG3") (pin "2") (pinfunction "GND_1_2") (pintype "bidirectional"))
      (node (ref "REG3") (pin "4") (pinfunction "GND_2_4") (pintype "bidirectional"))
      (node (ref "REG4") (pin "1") (pinfunction "ADJ/GND_1") (pintype "bidirectional"))
      (node (ref "REG5") (pin "2") (pinfunction "GND_1_2") (pintype "bidirectional"))
      (node (ref "REG5") (pin "4") (pinfunction "GND_2_4") (pintype "bidirectional"))
      (node (ref "REG6") (pin "1") (pinfunction "ADJ/GND_1") (pintype "bidirectional"))
      (node (ref "REG7") (pin "1") (pinfunction "ADJ/GND_1") (pintype "bidirectional"))
      (node (ref "REG8") (pin "1") (pinfunction "ADJ/GND_1") (pintype "bidirectional"))
      (node (ref "REG9") (pin "2") (pinfunction "GND_1_2") (pintype "bidirectional"))
      (node (ref "REG9") (pin "4") (pinfunction "GND_2_4") (pintype "bidirectional"))
      (node (ref "SPI_CTRL") (pin "1") (pinfunction "1_1") (pintype "bidirectional"))
      (node (ref "SPI_CTRL") (pin "11") (pinfunction "11_11") (pintype "bidirectional"))
      (node (ref "SPI_CTRL") (pin "13") (pinfunction "13_13") (pintype "bidirectional"))
      (node (ref "SPI_CTRL") (pin "15") (pinfunction "15_15") (pintype "bidirectional"))
      (node (ref "SPI_CTRL") (pin "3") (pinfunction "3_3") (pintype "bidirectional"))
      (node (ref "SPI_CTRL") (pin "5") (pinfunction "5_5") (pintype "bidirectional"))
      (node (ref "SPI_CTRL") (pin "7") (pinfunction "7_7") (pintype "bidirectional"))
      (node (ref "SPI_CTRL") (pin "9") (pinfunction "9_9") (pintype "bidirectional"))
      (node (ref "SYNC_CLK1") (pin "2") (pinfunction "2_2") (pintype "passive"))
      (node (ref "SYNC_CLK1") (pin "3") (pinfunction "2_3") (pintype "passive"))
      (node (ref "SYNC_CLK1") (pin "4") (pinfunction "2_4") (pintype "passive"))
      (node (ref "SYNC_CLK1") (pin "5") (pinfunction "2_5") (pintype "passive"))
      (node (ref "SYNC_CLK2") (pin "2") (pinfunction "2_2") (pintype "passive"))
      (node (ref "SYNC_CLK2") (pin "3") (pinfunction "2_3") (pintype "passive"))
      (node (ref "SYNC_CLK2") (pin "4") (pinfunction "2_4") (pintype "passive"))
      (node (ref "SYNC_CLK2") (pin "5") (pinfunction "2_5") (pintype "passive"))
      (node (ref "SYNC_IN+1") (pin "2") (pinfunction "2_2") (pintype "passive"))
      (node (ref "SYNC_IN+1") (pin "3") (pinfunction "2_3") (pintype "passive"))
      (node (ref "SYNC_IN+1") (pin "4") (pinfunction "2_4") (pintype "passive"))
      (node (ref "SYNC_IN+1") (pin "5") (pinfunction "2_5") (pintype "passive"))
      (node (ref "SYNC_IN+2") (pin "2") (pinfunction "2_2") (pintype "passive"))
      (node (ref "SYNC_IN+2") (pin "3") (pinfunction "2_3") (pintype "passive"))
      (node (ref "SYNC_IN+2") (pin "4") (pinfunction "2_4") (pintype "passive"))
      (node (ref "SYNC_IN+2") (pin "5") (pinfunction "2_5") (pintype "passive"))
      (node (ref "SYNC_IN-1") (pin "2") (pinfunction "2_2") (pintype "passive"))
      (node (ref "SYNC_IN-1") (pin "3") (pinfunction "2_3") (pintype "passive"))
      (node (ref "SYNC_IN-1") (pin "4") (pinfunction "2_4") (pintype "passive"))
      (node (ref "SYNC_IN-1") (pin "5") (pinfunction "2_5") (pintype "passive"))
      (node (ref "SYNC_IN-2") (pin "2") (pinfunction "2_2") (pintype "passive"))
      (node (ref "SYNC_IN-2") (pin "3") (pinfunction "2_3") (pintype "passive"))
      (node (ref "SYNC_IN-2") (pin "4") (pinfunction "2_4") (pintype "passive"))
      (node (ref "SYNC_IN-2") (pin "5") (pinfunction "2_5") (pintype "passive"))
      (node (ref "SYNC_OUT+1") (pin "2") (pinfunction "2_2") (pintype "passive"))
      (node (ref "SYNC_OUT+1") (pin "3") (pinfunction "2_3") (pintype "passive"))
      (node (ref "SYNC_OUT+1") (pin "4") (pinfunction "2_4") (pintype "passive"))
      (node (ref "SYNC_OUT+1") (pin "5") (pinfunction "2_5") (pintype "passive"))
      (node (ref "SYNC_OUT+2") (pin "2") (pinfunction "2_2") (pintype "passive"))
      (node (ref "SYNC_OUT+2") (pin "3") (pinfunction "2_3") (pintype "passive"))
      (node (ref "SYNC_OUT+2") (pin "4") (pinfunction "2_4") (pintype "passive"))
      (node (ref "SYNC_OUT+2") (pin "5") (pinfunction "2_5") (pintype "passive"))
      (node (ref "SYNC_OUT-1") (pin "2") (pinfunction "2_2") (pintype "passive"))
      (node (ref "SYNC_OUT-1") (pin "3") (pinfunction "2_3") (pintype "passive"))
      (node (ref "SYNC_OUT-1") (pin "4") (pinfunction "2_4") (pintype "passive"))
      (node (ref "SYNC_OUT-1") (pin "5") (pinfunction "2_5") (pintype "passive"))
      (node (ref "SYNC_OUT-2") (pin "2") (pinfunction "2_2") (pintype "passive"))
      (node (ref "SYNC_OUT-2") (pin "3") (pinfunction "2_3") (pintype "passive"))
      (node (ref "SYNC_OUT-2") (pin "4") (pinfunction "2_4") (pintype "passive"))
      (node (ref "SYNC_OUT-2") (pin "5") (pinfunction "2_5") (pintype "passive"))
      (node (ref "T1") (pin "2") (pinfunction "2_2") (pintype "passive"))
      (node (ref "T1") (pin "6") (pinfunction "6_6") (pintype "passive"))
      (node (ref "T2") (pin "2") (pinfunction "2_2") (pintype "bidirectional"))
      (node (ref "T2") (pin "4") (pinfunction "4_4") (pintype "passive"))
      (node (ref "T3") (pin "2") (pinfunction "2_2") (pintype "bidirectional"))
      (node (ref "T3") (pin "4") (pinfunction "4_4") (pintype "passive"))
      (node (ref "T4") (pin "6") (pinfunction "6_6") (pintype "passive"))
      (node (ref "U1") (pin "101") (pinfunction "EP_101") (pintype "passive"))
      (node (ref "U1") (pin "13") (pinfunction "DGND_2_13") (pintype "passive"))
      (node (ref "U1") (pin "16") (pinfunction "DGND_3_16") (pintype "passive"))
      (node (ref "U1") (pin "2") (pinfunction "PLL_LOOP_FILTER_2") (pintype "input"))
      (node (ref "U1") (pin "22") (pinfunction "DGND_4_22") (pintype "passive"))
      (node (ref "U1") (pin "29") (pinfunction "DGND_6_29") (pintype "passive"))
      (node (ref "U1") (pin "4") (pinfunction "AGND_6_4") (pintype "passive"))
      (node (ref "U1") (pin "46") (pinfunction "DGND_8_46") (pintype "passive"))
      (node (ref "U1") (pin "5") (pinfunction "AGND_8_5") (pintype "passive"))
      (node (ref "U1") (pin "51") (pinfunction "DGND_51") (pintype "passive"))
      (node (ref "U1") (pin "58") (pinfunction "DGND_5_58") (pintype "passive"))
      (node (ref "U1") (pin "65") (pinfunction "DGND_7_65") (pintype "passive"))
      (node (ref "U1") (pin "68") (pinfunction "SDO_68") (pintype "output"))
      (node (ref "U1") (pin "71") (pinfunction "I/O_RESET_71") (pintype "input"))
      (node (ref "U1") (pin "73") (pinfunction "AGND_9_73") (pintype "passive"))
      (node (ref "U1") (pin "78") (pinfunction "AGND_2_78") (pintype "passive"))
      (node (ref "U1") (pin "79") (pinfunction "AGND_3_79") (pintype "passive"))
      (node (ref "U1") (pin "82") (pinfunction "AGND_82") (pintype "passive"))
      (node (ref "U1") (pin "85") (pinfunction "AGND_5_85") (pintype "passive"))
      (node (ref "U1") (pin "88") (pinfunction "AGND_4_88") (pintype "passive"))
      (node (ref "U1") (pin "95") (pinfunction "XTAL_SEL_95") (pintype "input"))
      (node (ref "U1") (pin "96") (pinfunction "AGND_7_96") (pintype "passive"))
      (node (ref "U2") (pin "101") (pinfunction "EP_101") (pintype "passive"))
      (node (ref "U2") (pin "13") (pinfunction "DGND_2_13") (pintype "passive"))
      (node (ref "U2") (pin "16") (pinfunction "DGND_3_16") (pintype "passive"))
      (node (ref "U2") (pin "2") (pinfunction "PLL_LOOP_FILTER_2") (pintype "input"))
      (node (ref "U2") (pin "22") (pinfunction "DGND_4_22") (pintype "passive"))
      (node (ref "U2") (pin "29") (pinfunction "DGND_6_29") (pintype "passive"))
      (node (ref "U2") (pin "4") (pinfunction "AGND_6_4") (pintype "passive"))
      (node (ref "U2") (pin "46") (pinfunction "DGND_8_46") (pintype "passive"))
      (node (ref "U2") (pin "5") (pinfunction "AGND_8_5") (pintype "passive"))
      (node (ref "U2") (pin "51") (pinfunction "DGND_51") (pintype "passive"))
      (node (ref "U2") (pin "58") (pinfunction "DGND_5_58") (pintype "passive"))
      (node (ref "U2") (pin "65") (pinfunction "DGND_7_65") (pintype "passive"))
      (node (ref "U2") (pin "68") (pinfunction "SDO_68") (pintype "output"))
      (node (ref "U2") (pin "71") (pinfunction "I/O_RESET_71") (pintype "input"))
      (node (ref "U2") (pin "73") (pinfunction "AGND_9_73") (pintype "passive"))
      (node (ref "U2") (pin "78") (pinfunction "AGND_2_78") (pintype "passive"))
      (node (ref "U2") (pin "79") (pinfunction "AGND_3_79") (pintype "passive"))
      (node (ref "U2") (pin "82") (pinfunction "AGND_82") (pintype "passive"))
      (node (ref "U2") (pin "85") (pinfunction "AGND_5_85") (pintype "passive"))
      (node (ref "U2") (pin "88") (pinfunction "AGND_4_88") (pintype "passive"))
      (node (ref "U2") (pin "95") (pinfunction "XTAL_SEL_95") (pintype "input"))
      (node (ref "U2") (pin "96") (pinfunction "AGND_7_96") (pintype "passive"))
    )
    (net (code "79") (name "IOUT2_N") (class "Default")
      (node (ref "R14") (pin "2") (pinfunction "2_2") (pintype "bidirectional"))
      (node (ref "T4") (pin "1") (pinfunction "1_1") (pintype "passive"))
      (node (ref "U2") (pin "80") (pinfunction "IOUT*_80") (pintype "output"))
    )
    (net (code "80") (name "IOUT2_P") (class "Default")
      (node (ref "R13") (pin "1") (pinfunction "1_1") (pintype "bidirectional"))
      (node (ref "T4") (pin "3") (pinfunction "3_3") (pintype "passive"))
      (node (ref "U2") (pin "81") (pinfunction "IOUT_81") (pintype "output"))
    )
    (net (code "81") (name "IOUT_N") (class "Default")
      (node (ref "R7") (pin "2") (pinfunction "2_2") (pintype "bidirectional"))
      (node (ref "T1") (pin "1") (pinfunction "1_1") (pintype "passive"))
      (node (ref "U1") (pin "80") (pinfunction "IOUT*_80") (pintype "output"))
    )
    (net (code "82") (name "IOUT_P") (class "Default")
      (node (ref "R1") (pin "1") (pinfunction "1_1") (pintype "bidirectional"))
      (node (ref "T1") (pin "3") (pinfunction "3_3") (pintype "passive"))
      (node (ref "U1") (pin "81") (pinfunction "IOUT_81") (pintype "output"))
    )
    (net (code "83") (name "I{slash}O_UPDATE_1") (class "Default")
      (node (ref "PROFILE") (pin "8") (pinfunction "8_8") (pintype "bidirectional"))
      (node (ref "U1") (pin "59") (pinfunction "I/O_UPDATE_59") (pintype "bidirectional"))
    )
    (net (code "84") (name "I{slash}O_UPDATE_2") (class "Default")
      (node (ref "PROFILE") (pin "10") (pinfunction "10_10") (pintype "bidirectional"))
      (node (ref "U2") (pin "59") (pinfunction "I/O_UPDATE_59") (pintype "bidirectional"))
    )
    (net (code "85") (name "MASTER_RESET") (class "Default")
      (node (ref "SPI_CTRL") (pin "2") (pinfunction "2_2") (pintype "bidirectional"))
      (node (ref "U1") (pin "14") (pinfunction "MASTER_RESET_14") (pintype "input"))
    )
    (net (code "86") (name "MASTER_RESET2") (class "Default")
      (node (ref "SPI_CTRL") (pin "16") (pinfunction "16_16") (pintype "bidirectional"))
      (node (ref "U2") (pin "14") (pinfunction "MASTER_RESET_14") (pintype "input"))
    )
    (net (code "87") (name "Net-(C51-Pad1)") (class "Default")
      (node (ref "C51") (pin "1") (pinfunction "1_1") (pintype "passive"))
      (node (ref "R41") (pin "2") (pinfunction "2_2") (pintype "bidirectional"))
      (node (ref "T2") (pin "3") (pinfunction "3_3") (pintype "passive"))
    )
    (net (code "88") (name "Net-(C52-Pad2)") (class "Default")
      (node (ref "C52") (pin "2") (pinfunction "2_2") (pintype "passive"))
      (node (ref "R42") (pin "2") (pinfunction "2_2") (pintype "bidirectional"))
      (node (ref "T2") (pin "1") (pinfunction "1_1") (pintype "passive"))
    )
    (net (code "89") (name "Net-(C97-Pad1)") (class "Default")
      (node (ref "C97") (pin "1") (pinfunction "1_1") (pintype "passive"))
      (node (ref "R15") (pin "2") (pinfunction "2_2") (pintype "bidirectional"))
      (node (ref "T3") (pin "3") (pinfunction "3_3") (pintype "passive"))
    )
    (net (code "90") (name "Net-(C98-Pad1)") (class "Default")
      (node (ref "C98") (pin "1") (pinfunction "1_1") (pintype "passive"))
      (node (ref "R16") (pin "2") (pinfunction "2_2") (pintype "bidirectional"))
      (node (ref "T3") (pin "1") (pinfunction "1_1") (pintype "passive"))
    )
    (net (code "91") (name "Net-(C100-Pad1)") (class "Default")
      (node (ref "C100") (pin "1") (pinfunction "1_1") (pintype "bidirectional"))
      (node (ref "C105") (pin "1") (pinfunction "1_1") (pintype "bidirectional"))
      (node (ref "C125") (pin "2") (pinfunction "2_2") (pintype "bidirectional"))
      (node (ref "C126") (pin "1") (pinfunction "1_1") (pintype "bidirectional"))
      (node (ref "L5") (pin "2") (pinfunction "2_2") (pintype "bidirectional"))
      (node (ref "L6") (pin "1") (pinfunction "1_1") (pintype "bidirectional"))
    )
    (net (code "92") (name "Net-(C101-Pad1)") (class "Default")
      (node (ref "C101") (pin "1") (pinfunction "1_1") (pintype "bidirectional"))
      (node (ref "C106") (pin "1") (pinfunction "1_1") (pintype "bidirectional"))
      (node (ref "C126") (pin "2") (pinfunction "2_2") (pintype "bidirectional"))
      (node (ref "FILTERED_OUT2") (pin "1") (pinfunction "1_1") (pintype "passive"))
      (node (ref "L6") (pin "2") (pinfunction "2_2") (pintype "bidirectional"))
    )
    (net (code "93") (name "Net-(C102-Pad1)") (class "Default")
      (node (ref "C102") (pin "1") (pinfunction "1_1") (pintype "bidirectional"))
      (node (ref "C103") (pin "1") (pinfunction "1_1") (pintype "bidirectional"))
      (node (ref "C124") (pin "1") (pinfunction "1_1") (pintype "bidirectional"))
      (node (ref "L4") (pin "1") (pinfunction "1_1") (pintype "bidirectional"))
      (node (ref "T4") (pin "4") (pinfunction "4_4") (pintype "passive"))
    )
    (net (code "94") (name "Net-(C104-Pad1)") (class "Default")
      (node (ref "C104") (pin "1") (pinfunction "1_1") (pintype "bidirectional"))
      (node (ref "C124") (pin "2") (pinfunction "2_2") (pintype "bidirectional"))
      (node (ref "C125") (pin "1") (pinfunction "1_1") (pintype "bidirectional"))
      (node (ref "C99") (pin "1") (pinfunction "1_1") (pintype "bidirectional"))
      (node (ref "L4") (pin "2") (pinfunction "2_2") (pintype "bidirectional"))
      (node (ref "L5") (pin "1") (pinfunction "1_1") (pintype "bidirectional"))
    )
    (net (code "95") (name "Net-(C121-Pad1)") (class "Default")
      (node (ref "C121") (pin "1") (pinfunction "1_1") (pintype "bidirectional"))
      (node (ref "C25") (pin "1") (pinfunction "1_1") (pintype "bidirectional"))
      (node (ref "C53") (pin "1") (pinfunction "1_1") (pintype "bidirectional"))
      (node (ref "L1") (pin "1") (pinfunction "1_1") (pintype "bidirectional"))
      (node (ref "T1") (pin "4") (pinfunction "4_4") (pintype "passive"))
    )
    (net (code "96") (name "Net-(C121-Pad2)") (class "Default")
      (node (ref "C121") (pin "2") (pinfunction "2_2") (pintype "bidirectional"))
      (node (ref "C122") (pin "1") (pinfunction "1_1") (pintype "bidirectional"))
      (node (ref "C26") (pin "1") (pinfunction "1_1") (pintype "bidirectional"))
      (node (ref "C54") (pin "1") (pinfunction "1_1") (pintype "bidirectional"))
      (node (ref "L1") (pin "2") (pinfunction "2_2") (pintype "bidirectional"))
      (node (ref "L2") (pin "1") (pinfunction "1_1") (pintype "bidirectional"))
    )
    (net (code "97") (name "Net-(C122-Pad2)") (class "Default")
      (node (ref "C122") (pin "2") (pinfunction "2_2") (pintype "bidirectional"))
      (node (ref "C123") (pin "1") (pinfunction "1_1") (pintype "bidirectional"))
      (node (ref "C27") (pin "1") (pinfunction "1_1") (pintype "bidirectional"))
      (node (ref "C55") (pin "1") (pinfunction "1_1") (pintype "bidirectional"))
      (node (ref "L2") (pin "2") (pinfunction "2_2") (pintype "bidirectional"))
      (node (ref "L3") (pin "1") (pinfunction "1_1") (pintype "bidirectional"))
    )
    (net (code "98") (name "Net-(C123-Pad2)") (class "Default")
      (node (ref "C123") (pin "2") (pinfunction "2_2") (pintype "bidirectional"))
      (node (ref "C28") (pin "1") (pinfunction "1_1") (pintype "bidirectional"))
      (node (ref "C56") (pin "1") (pinfunction "1_1") (pintype "bidirectional"))
      (node (ref "FILTERED_OUT") (pin "1") (pinfunction "1_1") (pintype "passive"))
      (node (ref "L3") (pin "2") (pinfunction "2_2") (pintype "bidirectional"))
    )
    (net (code "99") (name "Net-(LED5-K)") (class "Default")
      (node (ref "LED5") (pin "1") (pinfunction "K_1") (pintype "bidirectional"))
      (node (ref "R27") (pin "2") (pinfunction "2_2") (pintype "passive"))
    )
    (net (code "100") (name "Net-(PS1A-P1)") (class "Default")
      (node (ref "PS1") (pin "3") (pinfunction "P1_3") (pintype "bidirectional"))
      (node (ref "T2") (pin "5") (pinfunction "5_5") (pintype "passive"))
    )
    (net (code "101") (name "Net-(PS1A-P2)") (class "Default")
      (node (ref "PS1") (pin "4") (pinfunction "P2_4") (pintype "bidirectional"))
      (node (ref "T3") (pin "5") (pinfunction "5_5") (pintype "passive"))
    )
    (net (code "102") (name "OSK1") (class "Default")
      (node (ref "RAMP1") (pin "2") (pinfunction "2_2") (pintype "bidirectional"))
      (node (ref "U1") (pin "60") (pinfunction "OSK_60") (pintype "input"))
    )
    (net (code "103") (name "OSK2") (class "Default")
      (node (ref "RAMP2") (pin "2") (pinfunction "2_2") (pintype "bidirectional"))
      (node (ref "U2") (pin "60") (pinfunction "OSK_60") (pintype "input"))
    )
    (net (code "104") (name "PLL_LOCK") (class "Default")
      (node (ref "TP2") (pin "TP") (pinfunction "TP_TP") (pintype "input"))
      (node (ref "U1") (pin "19") (pinfunction "PLL_LOCK_19") (pintype "output"))
    )
    (net (code "105") (name "PLL_LOCK2") (class "Default")
      (node (ref "TP4") (pin "TP") (pinfunction "TP_TP") (pintype "input"))
      (node (ref "U2") (pin "19") (pinfunction "PLL_LOCK_19") (pintype "output"))
    )
    (net (code "106") (name "PROFILE0") (class "Default")
      (node (ref "PROFILE") (pin "6") (pinfunction "6_6") (pintype "bidirectional"))
      (node (ref "U1") (pin "54") (pinfunction "PROFILE0_54") (pintype "input"))
    )
    (net (code "107") (name "PROFILE0-2") (class "Default")
      (node (ref "PROFILE") (pin "12") (pinfunction "12_12") (pintype "bidirectional"))
      (node (ref "U2") (pin "54") (pinfunction "PROFILE0_54") (pintype "input"))
    )
    (net (code "108") (name "PROFILE1") (class "Default")
      (node (ref "PROFILE") (pin "4") (pinfunction "4_4") (pintype "bidirectional"))
      (node (ref "U1") (pin "53") (pinfunction "PROFILE1_53") (pintype "input"))
    )
    (net (code "109") (name "PROFILE1-2") (class "Default")
      (node (ref "PROFILE") (pin "14") (pinfunction "14_14") (pintype "bidirectional"))
      (node (ref "U2") (pin "53") (pinfunction "PROFILE1_53") (pintype "input"))
    )
    (net (code "110") (name "PROFILE2") (class "Default")
      (node (ref "PROFILE") (pin "2") (pinfunction "2_2") (pintype "bidirectional"))
      (node (ref "U1") (pin "52") (pinfunction "PROFILE2_52") (pintype "input"))
    )
    (net (code "111") (name "PROFILE2-2") (class "Default")
      (node (ref "PROFILE") (pin "16") (pinfunction "16_16") (pintype "bidirectional"))
      (node (ref "U2") (pin "52") (pinfunction "PROFILE2_52") (pintype "input"))
    )
    (net (code "112") (name "PWR") (class "Default")
      (node (ref "D1") (pin "1") (pinfunction "K_1") (pintype "power_in"))
      (node (ref "J1") (pin "1") (pinfunction "1_1") (pintype "passive"))
      (node (ref "SW1") (pin "2") (pinfunction "COM_2") (pintype "bidirectional"))
    )
    (net (code "113") (name "RAM_SWP_OVER") (class "Default")
      (node (ref "TP6") (pin "TP") (pinfunction "TP_TP") (pintype "input"))
      (node (ref "U1") (pin "24") (pinfunction "RAM_SWP_OVR_24") (pintype "output"))
    )
    (net (code "114") (name "RAM_SWP_OVER2") (class "Default")
      (node (ref "TP9") (pin "TP") (pinfunction "TP_TP") (pintype "input"))
      (node (ref "U2") (pin "24") (pinfunction "RAM_SWP_OVR_24") (pintype "output"))
    )
    (net (code "115") (name "REFCLK2_N") (class "Default")
      (node (ref "C51") (pin "2") (pinfunction "2_2") (pintype "passive"))
      (node (ref "U2") (pin "91") (pinfunction "REF_CLK*_91") (pintype "input"))
    )
    (net (code "116") (name "REFCLK2_P") (class "Default")
      (node (ref "C52") (pin "1") (pinfunction "1_1") (pintype "passive"))
      (node (ref "U2") (pin "90") (pinfunction "REF_CLK_90") (pintype "input"))
    )
    (net (code "117") (name "REFCLK_N") (class "Default")
      (node (ref "C97") (pin "2") (pinfunction "2_2") (pintype "passive"))
      (node (ref "U1") (pin "91") (pinfunction "REF_CLK*_91") (pintype "input"))
    )
    (net (code "118") (name "REFCLK_OUT") (class "Default")
      (node (ref "TP1") (pin "TP") (pinfunction "TP_TP") (pintype "input"))
      (node (ref "U1") (pin "94") (pinfunction "REFCLK_OUT_94") (pintype "output"))
    )
    (net (code "119") (name "REFCLK_OUT2") (class "Default")
      (node (ref "TP3") (pin "TP") (pinfunction "TP_TP") (pintype "input"))
      (node (ref "U2") (pin "94") (pinfunction "REFCLK_OUT_94") (pintype "output"))
    )
    (net (code "120") (name "REFCLK_P") (class "Default")
      (node (ref "C98") (pin "2") (pinfunction "2_2") (pintype "passive"))
      (node (ref "U1") (pin "90") (pinfunction "REF_CLK_90") (pintype "input"))
    )
    (net (code "121") (name "SCLK") (class "Default")
      (node (ref "SPI_CTRL") (pin "6") (pinfunction "6_6") (pintype "bidirectional"))
      (node (ref "U1") (pin "69") (pinfunction "SCLK_69") (pintype "input"))
    )
    (net (code "122") (name "SCLK2") (class "Default")
      (node (ref "SPI_CTRL") (pin "12") (pinfunction "12_12") (pintype "bidirectional"))
      (node (ref "U2") (pin "69") (pinfunction "SCLK_69") (pintype "input"))
    )
    (net (code "123") (name "SDIO") (class "Default")
      (node (ref "SPI_CTRL") (pin "4") (pinfunction "4_4") (pintype "bidirectional"))
      (node (ref "U1") (pin "67") (pinfunction "SDIO_67") (pintype "bidirectional"))
    )
    (net (code "124") (name "SDIO2") (class "Default")
      (node (ref "SPI_CTRL") (pin "14") (pinfunction "14_14") (pintype "bidirectional"))
      (node (ref "U2") (pin "67") (pinfunction "SDIO_67") (pintype "bidirectional"))
    )
    (net (code "125") (name "SYNCIN1_N") (class "Default")
      (node (ref "SYNC_IN-1") (pin "1") (pinfunction "1_1") (pintype "passive"))
      (node (ref "U1") (pin "8") (pinfunction "SYNC_IN-_8") (pintype "input"))
    )
    (net (code "126") (name "SYNCIN1_P") (class "Default")
      (node (ref "SYNC_IN+1") (pin "1") (pinfunction "1_1") (pintype "passive"))
      (node (ref "U1") (pin "7") (pinfunction "SYNC_IN+_7") (pintype "input"))
    )
    (net (code "127") (name "SYNCIN2_N") (class "Default")
      (node (ref "SYNC_IN-2") (pin "1") (pinfunction "1_1") (pintype "passive"))
      (node (ref "U2") (pin "8") (pinfunction "SYNC_IN-_8") (pintype "input"))
    )
    (net (code "128") (name "SYNCIN2_P") (class "Default")
      (node (ref "SYNC_IN+2") (pin "1") (pinfunction "1_1") (pintype "passive"))
      (node (ref "U2") (pin "7") (pinfunction "SYNC_IN+_7") (pintype "input"))
    )
    (net (code "129") (name "SYNCOUT1_N") (class "Default")
      (node (ref "R29") (pin "1") (pinfunction "1_1") (pintype "bidirectional"))
      (node (ref "SYNC_OUT-1") (pin "1") (pinfunction "1_1") (pintype "passive"))
      (node (ref "U1") (pin "10") (pinfunction "SYNC_OUT-_10") (pintype "output"))
    )
    (net (code "130") (name "SYNCOUT1_P") (class "Default")
      (node (ref "R29") (pin "2") (pinfunction "2_2") (pintype "bidirectional"))
      (node (ref "SYNC_OUT+1") (pin "1") (pinfunction "1_1") (pintype "passive"))
      (node (ref "U1") (pin "9") (pinfunction "SYNC_OUT+_9") (pintype "output"))
    )
    (net (code "131") (name "SYNCOUT2_N") (class "Default")
      (node (ref "R36") (pin "1") (pinfunction "1_1") (pintype "bidirectional"))
      (node (ref "SYNC_OUT-2") (pin "1") (pinfunction "1_1") (pintype "passive"))
      (node (ref "U2") (pin "10") (pinfunction "SYNC_OUT-_10") (pintype "output"))
    )
    (net (code "132") (name "SYNCOUT2_P") (class "Default")
      (node (ref "R36") (pin "2") (pinfunction "2_2") (pintype "bidirectional"))
      (node (ref "SYNC_OUT+2") (pin "1") (pinfunction "1_1") (pintype "passive"))
      (node (ref "U2") (pin "9") (pinfunction "SYNC_OUT+_9") (pintype "output"))
    )
    (net (code "133") (name "SYNC_SMP_ERR") (class "Default")
      (node (ref "TP7") (pin "TP") (pinfunction "TP_TP") (pintype "input"))
      (node (ref "U1") (pin "12") (pinfunction "SYNC_SMP_ERR_12") (pintype "output"))
    )
    (net (code "134") (name "SYNC_SMP_ERR2") (class "Default")
      (node (ref "TP10") (pin "TP") (pinfunction "TP_TP") (pintype "input"))
      (node (ref "U2") (pin "12") (pinfunction "SYNC_SMP_ERR_12") (pintype "output"))
    )
    (net (code "135") (name "TXENABLE1") (class "Default")
      (node (ref "PARALLEL1") (pin "26") (pinfunction "26_26") (pintype "bidirectional"))
      (node (ref "U1") (pin "41") (pinfunction "TXENABLE_41") (pintype "input"))
    )
    (net (code "136") (name "TXENABLE2") (class "Default")
      (node (ref "PARALLEL2") (pin "26") (pinfunction "26_26") (pintype "bidirectional"))
      (node (ref "U2") (pin "41") (pinfunction "TXENABLE_41") (pintype "input"))
    )
    (net (code "137") (name "VCC") (class "Default")
      (node (ref "C112") (pin "1") (pinfunction "+_1") (pintype "bidirectional"))
      (node (ref "C117") (pin "1") (pinfunction "+_1") (pintype "bidirectional"))
      (node (ref "C18") (pin "1") (pinfunction "+_1") (pintype "bidirectional"))
      (node (ref "C22") (pin "1") (pinfunction "+_1") (pintype "bidirectional"))
      (node (ref "C34") (pin "1") (pinfunction "+_1") (pintype "bidirectional"))
      (node (ref "C39") (pin "1") (pinfunction "+_1") (pintype "bidirectional"))
      (node (ref "C42") (pin "1") (pinfunction "+_1") (pintype "bidirectional"))
      (node (ref "C46") (pin "1") (pinfunction "+_1") (pintype "bidirectional"))
      (node (ref "C47") (pin "1") (pinfunction "+_1") (pintype "bidirectional"))
      (node (ref "C48") (pin "1") (pinfunction "+_1") (pintype "bidirectional"))
      (node (ref "C49") (pin "1") (pinfunction "+_1") (pintype "bidirectional"))
      (node (ref "C9") (pin "1") (pinfunction "+_1") (pintype "bidirectional"))
      (node (ref "LED5") (pin "2") (pinfunction "A_2") (pintype "bidirectional"))
      (node (ref "REG1") (pin "3") (pinfunction "INPUT_3") (pintype "bidirectional"))
      (node (ref "REG10") (pin "3") (pinfunction "INPUT_3") (pintype "bidirectional"))
      (node (ref "REG11") (pin "1") (pinfunction "IN_1") (pintype "bidirectional"))
      (node (ref "REG12") (pin "3") (pinfunction "INPUT_3") (pintype "bidirectional"))
      (node (ref "REG2") (pin "3") (pinfunction "INPUT_3") (pintype "bidirectional"))
      (node (ref "REG3") (pin "1") (pinfunction "IN_1") (pintype "bidirectional"))
      (node (ref "REG4") (pin "3") (pinfunction "INPUT_3") (pintype "bidirectional"))
      (node (ref "REG5") (pin "1") (pinfunction "IN_1") (pintype "bidirectional"))
      (node (ref "REG6") (pin "3") (pinfunction "INPUT_3") (pintype "bidirectional"))
      (node (ref "REG7") (pin "3") (pinfunction "INPUT_3") (pintype "bidirectional"))
      (node (ref "REG8") (pin "3") (pinfunction "INPUT_3") (pintype "bidirectional"))
      (node (ref "REG9") (pin "1") (pinfunction "IN_1") (pintype "bidirectional"))
      (node (ref "SW1") (pin "3") (pinfunction "P$3_3") (pintype "bidirectional"))
    )
    (net (code "138") (name "unconnected-(SW1-P$2-Pad1)") (class "Default")
      (node (ref "SW1") (pin "1") (pinfunction "P$2_1") (pintype "bidirectional"))
    )
    (net (code "139") (name "unconnected-(T4-Pad2)") (class "Default")
      (node (ref "T4") (pin "2") (pinfunction "2_2") (pintype "passive"))
    )
    (net (code "140") (name "unconnected-(U1-NC-Pad72)") (class "Default")
      (node (ref "U1") (pin "72") (pinfunction "NC_72") (pintype "no_connect"))
    )
    (net (code "141") (name "unconnected-(U1-NC_2-Pad98)") (class "Default")
      (node (ref "U1") (pin "98") (pinfunction "NC_2_98") (pintype "no_connect"))
    )
    (net (code "142") (name "unconnected-(U1-NC_3-Pad1)") (class "Default")
      (node (ref "U1") (pin "1") (pinfunction "NC_3_1") (pintype "no_connect"))
    )
    (net (code "143") (name "unconnected-(U1-NC_4-Pad86)") (class "Default")
      (node (ref "U1") (pin "86") (pinfunction "NC_4_86") (pintype "no_connect"))
    )
    (net (code "144") (name "unconnected-(U1-NC_5-Pad87)") (class "Default")
      (node (ref "U1") (pin "87") (pinfunction "NC_5_87") (pintype "no_connect"))
    )
    (net (code "145") (name "unconnected-(U1-NC_6-Pad93)") (class "Default")
      (node (ref "U1") (pin "93") (pinfunction "NC_6_93") (pintype "no_connect"))
    )
    (net (code "146") (name "unconnected-(U1-NC_7-Pad97)") (class "Default")
      (node (ref "U1") (pin "97") (pinfunction "NC_7_97") (pintype "no_connect"))
    )
    (net (code "147") (name "unconnected-(U1-NC_8-Pad99)") (class "Default")
      (node (ref "U1") (pin "99") (pinfunction "NC_8_99") (pintype "no_connect"))
    )
    (net (code "148") (name "unconnected-(U1-NC_9-Pad20)") (class "Default")
      (node (ref "U1") (pin "20") (pinfunction "NC_9_20") (pintype "no_connect"))
    )
    (net (code "149") (name "unconnected-(U1-NC_10-Pad100)") (class "Default")
      (node (ref "U1") (pin "100") (pinfunction "NC_10_100") (pintype "no_connect"))
    )
    (net (code "150") (name "unconnected-(U2-NC-Pad72)") (class "Default")
      (node (ref "U2") (pin "72") (pinfunction "NC_72") (pintype "no_connect"))
    )
    (net (code "151") (name "unconnected-(U2-NC_2-Pad98)") (class "Default")
      (node (ref "U2") (pin "98") (pinfunction "NC_2_98") (pintype "no_connect"))
    )
    (net (code "152") (name "unconnected-(U2-NC_3-Pad1)") (class "Default")
      (node (ref "U2") (pin "1") (pinfunction "NC_3_1") (pintype "no_connect"))
    )
    (net (code "153") (name "unconnected-(U2-NC_4-Pad86)") (class "Default")
      (node (ref "U2") (pin "86") (pinfunction "NC_4_86") (pintype "no_connect"))
    )
    (net (code "154") (name "unconnected-(U2-NC_5-Pad87)") (class "Default")
      (node (ref "U2") (pin "87") (pinfunction "NC_5_87") (pintype "no_connect"))
    )
    (net (code "155") (name "unconnected-(U2-NC_6-Pad93)") (class "Default")
      (node (ref "U2") (pin "93") (pinfunction "NC_6_93") (pintype "no_connect"))
    )
    (net (code "156") (name "unconnected-(U2-NC_7-Pad97)") (class "Default")
      (node (ref "U2") (pin "97") (pinfunction "NC_7_97") (pintype "no_connect"))
    )
    (net (code "157") (name "unconnected-(U2-NC_8-Pad99)") (class "Default")
      (node (ref "U2") (pin "99") (pinfunction "NC_8_99") (pintype "no_connect"))
    )
    (net (code "158") (name "unconnected-(U2-NC_9-Pad20)") (class "Default")
      (node (ref "U2") (pin "20") (pinfunction "NC_9_20") (pintype "no_connect"))
    )
    (net (code "159") (name "unconnected-(U2-NC_10-Pad100)") (class "Default")
      (node (ref "U2") (pin "100") (pinfunction "NC_10_100") (pintype "no_connect"))
    )
  )
)
